# Mosfet.net
KiCad netlist of a schematic drawn in Altium Designer
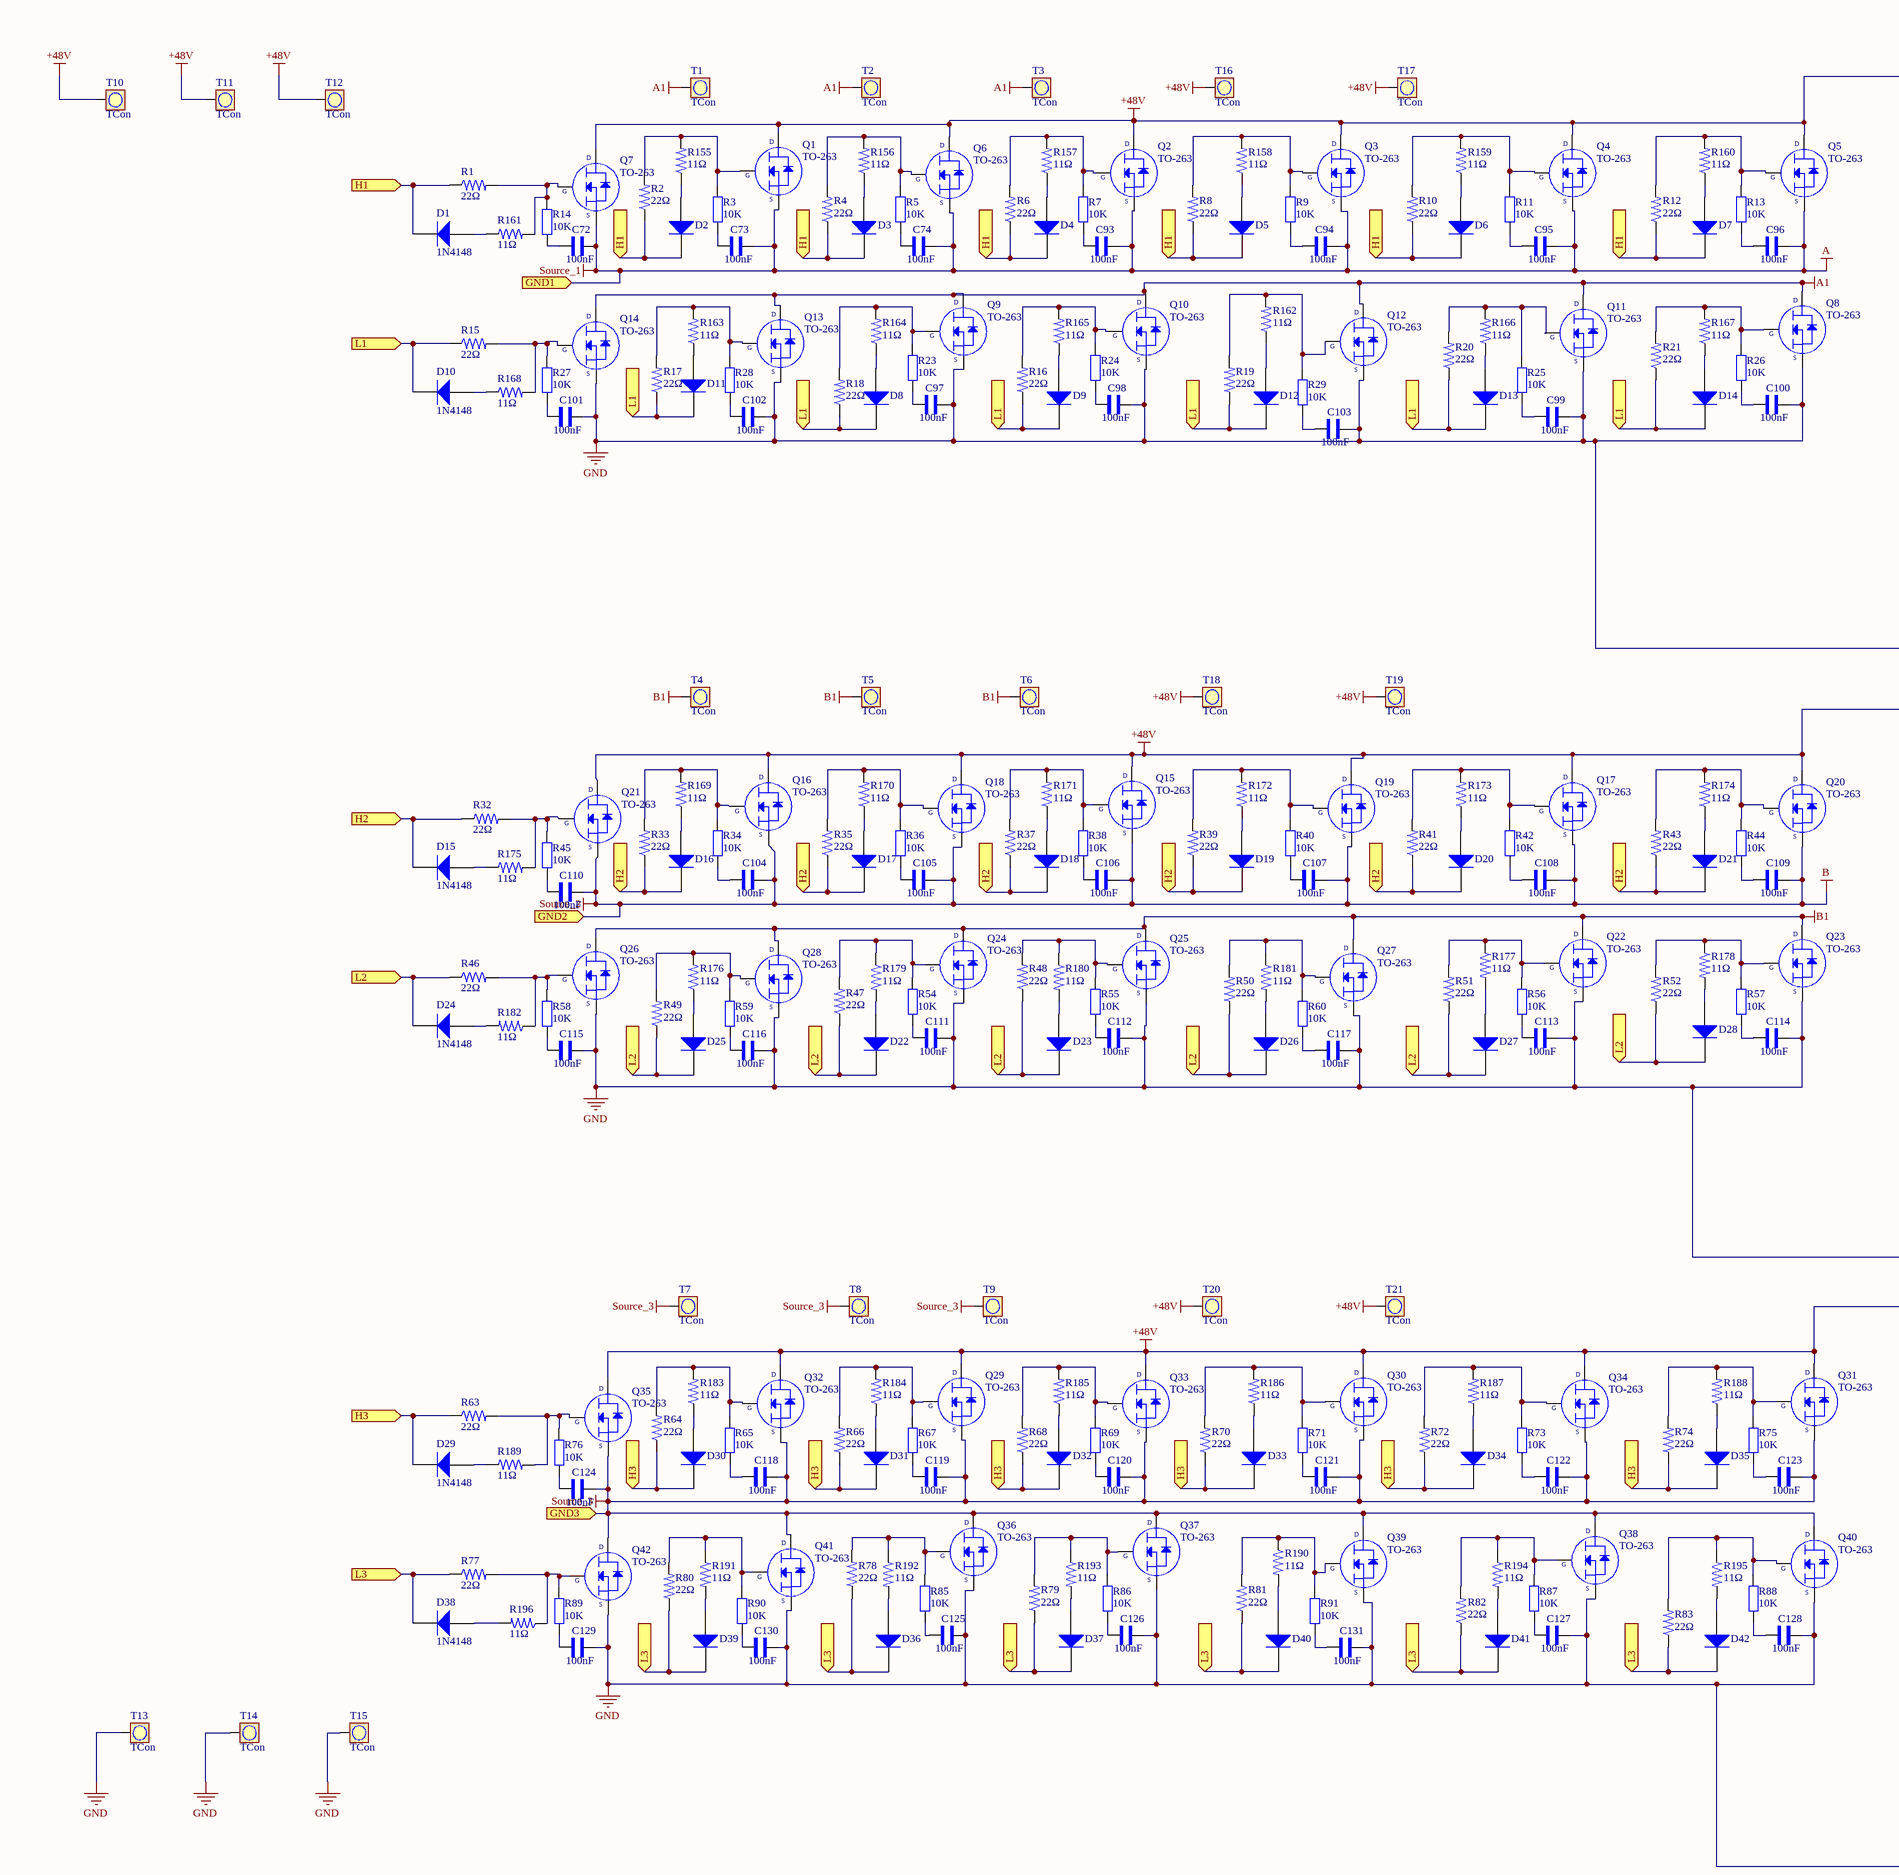
[diagram p0: Mosfet.SchDoc, left]
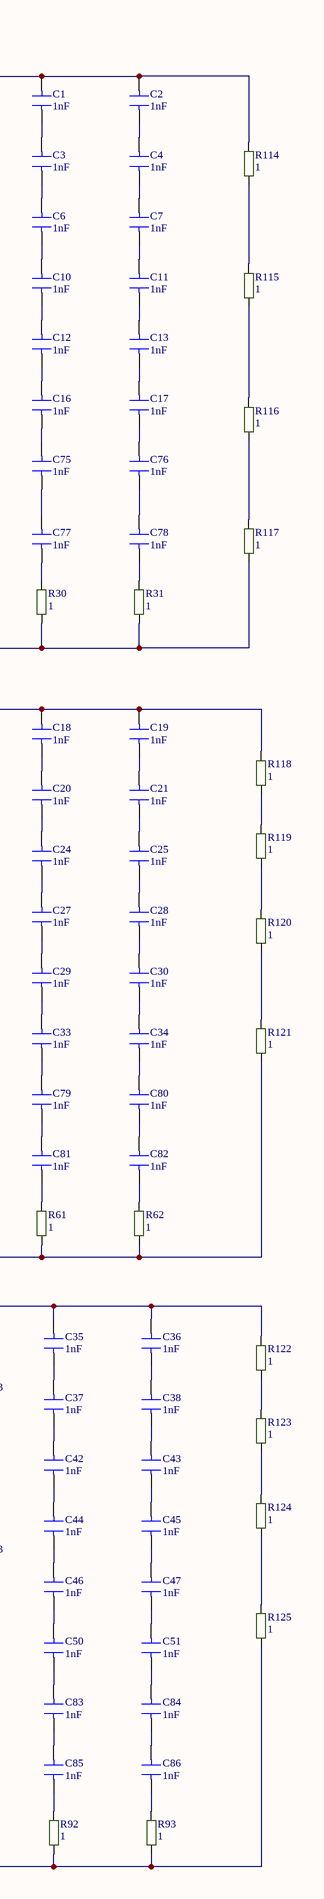
[diagram p1: Mosfet.SchDoc, right]

(export (version "E")
  (design (tool "Eeschema 10.0.6"))
  (components
    (comp (ref "C1")
      (value "1nF")
      (footprint "CAP 1206_3216 - 1.8MM")
      (libsource (lib "PROJE") (part "CAP 1nF 1206"))
    )
    (comp (ref "C2")
      (value "1nF")
      (footprint "CAP 1206_3216 - 1.8MM")
      (libsource (lib "PROJE") (part "CAP 1nF 1206"))
    )
    (comp (ref "C3")
      (value "1nF")
      (footprint "CAP 1206_3216 - 1.8MM")
      (libsource (lib "PROJE") (part "CAP 1nF 1206"))
    )
    (comp (ref "C4")
      (value "1nF")
      (footprint "CAP 1206_3216 - 1.8MM")
      (libsource (lib "PROJE") (part "CAP 1nF 1206"))
    )
    (comp (ref "C6")
      (value "1nF")
      (footprint "CAP 1206_3216 - 1.8MM")
      (libsource (lib "PROJE") (part "CAP 1nF 1206"))
    )
    (comp (ref "C7")
      (value "1nF")
      (footprint "CAP 1206_3216 - 1.8MM")
      (libsource (lib "PROJE") (part "CAP 1nF 1206"))
    )
    (comp (ref "C10")
      (value "1nF")
      (footprint "CAP 1206_3216 - 1.8MM")
      (libsource (lib "PROJE") (part "CAP 1nF 1206"))
    )
    (comp (ref "C11")
      (value "1nF")
      (footprint "CAP 1206_3216 - 1.8MM")
      (libsource (lib "PROJE") (part "CAP 1nF 1206"))
    )
    (comp (ref "C12")
      (value "1nF")
      (footprint "CAP 1206_3216 - 1.8MM")
      (libsource (lib "PROJE") (part "CAP 1nF 1206"))
    )
    (comp (ref "C13")
      (value "1nF")
      (footprint "CAP 1206_3216 - 1.8MM")
      (libsource (lib "PROJE") (part "CAP 1nF 1206"))
    )
    (comp (ref "C16")
      (value "1nF")
      (footprint "CAP 1206_3216 - 1.8MM")
      (libsource (lib "PROJE") (part "CAP 1nF 1206"))
    )
    (comp (ref "C17")
      (value "1nF")
      (footprint "CAP 1206_3216 - 1.8MM")
      (libsource (lib "PROJE") (part "CAP 1nF 1206"))
    )
    (comp (ref "C18")
      (value "1nF")
      (footprint "CAP 1206_3216 - 1.8MM")
      (libsource (lib "PROJE") (part "CAP 1nF 1206"))
    )
    (comp (ref "C19")
      (value "1nF")
      (footprint "CAP 1206_3216 - 1.8MM")
      (libsource (lib "PROJE") (part "CAP 1nF 1206"))
    )
    (comp (ref "C20")
      (value "1nF")
      (footprint "CAP 1206_3216 - 1.8MM")
      (libsource (lib "PROJE") (part "CAP 1nF 1206"))
    )
    (comp (ref "C21")
      (value "1nF")
      (footprint "CAP 1206_3216 - 1.8MM")
      (libsource (lib "PROJE") (part "CAP 1nF 1206"))
    )
    (comp (ref "C24")
      (value "1nF")
      (footprint "CAP 1206_3216 - 1.8MM")
      (libsource (lib "PROJE") (part "CAP 1nF 1206"))
    )
    (comp (ref "C25")
      (value "1nF")
      (footprint "CAP 1206_3216 - 1.8MM")
      (libsource (lib "PROJE") (part "CAP 1nF 1206"))
    )
    (comp (ref "C27")
      (value "1nF")
      (footprint "CAP 1206_3216 - 1.8MM")
      (libsource (lib "PROJE") (part "CAP 1nF 1206"))
    )
    (comp (ref "C28")
      (value "1nF")
      (footprint "CAP 1206_3216 - 1.8MM")
      (libsource (lib "PROJE") (part "CAP 1nF 1206"))
    )
    (comp (ref "C29")
      (value "1nF")
      (footprint "CAP 1206_3216 - 1.8MM")
      (libsource (lib "PROJE") (part "CAP 1nF 1206"))
    )
    (comp (ref "C30")
      (value "1nF")
      (footprint "CAP 1206_3216 - 1.8MM")
      (libsource (lib "PROJE") (part "CAP 1nF 1206"))
    )
    (comp (ref "C33")
      (value "1nF")
      (footprint "CAP 1206_3216 - 1.8MM")
      (libsource (lib "PROJE") (part "CAP 1nF 1206"))
    )
    (comp (ref "C34")
      (value "1nF")
      (footprint "CAP 1206_3216 - 1.8MM")
      (libsource (lib "PROJE") (part "CAP 1nF 1206"))
    )
    (comp (ref "C35")
      (value "1nF")
      (footprint "CAP 1206_3216 - 1.8MM")
      (libsource (lib "PROJE") (part "CAP 1nF 1206"))
    )
    (comp (ref "C36")
      (value "1nF")
      (footprint "CAP 1206_3216 - 1.8MM")
      (libsource (lib "PROJE") (part "CAP 1nF 1206"))
    )
    (comp (ref "C37")
      (value "1nF")
      (footprint "CAP 1206_3216 - 1.8MM")
      (libsource (lib "PROJE") (part "CAP 1nF 1206"))
    )
    (comp (ref "C38")
      (value "1nF")
      (footprint "CAP 1206_3216 - 1.8MM")
      (libsource (lib "PROJE") (part "CAP 1nF 1206"))
    )
    (comp (ref "C42")
      (value "1nF")
      (footprint "CAP 1206_3216 - 1.8MM")
      (libsource (lib "PROJE") (part "CAP 1nF 1206"))
    )
    (comp (ref "C43")
      (value "1nF")
      (footprint "CAP 1206_3216 - 1.8MM")
      (libsource (lib "PROJE") (part "CAP 1nF 1206"))
    )
    (comp (ref "C44")
      (value "1nF")
      (footprint "CAP 1206_3216 - 1.8MM")
      (libsource (lib "PROJE") (part "CAP 1nF 1206"))
    )
    (comp (ref "C45")
      (value "1nF")
      (footprint "CAP 1206_3216 - 1.8MM")
      (libsource (lib "PROJE") (part "CAP 1nF 1206"))
    )
    (comp (ref "C46")
      (value "1nF")
      (footprint "CAP 1206_3216 - 1.8MM")
      (libsource (lib "PROJE") (part "CAP 1nF 1206"))
    )
    (comp (ref "C47")
      (value "1nF")
      (footprint "CAP 1206_3216 - 1.8MM")
      (libsource (lib "PROJE") (part "CAP 1nF 1206"))
    )
    (comp (ref "C50")
      (value "1nF")
      (footprint "CAP 1206_3216 - 1.8MM")
      (libsource (lib "PROJE") (part "CAP 1nF 1206"))
    )
    (comp (ref "C51")
      (value "1nF")
      (footprint "CAP 1206_3216 - 1.8MM")
      (libsource (lib "PROJE") (part "CAP 1nF 1206"))
    )
    (comp (ref "C72")
      (value "100nF")
      (footprint "C-0805W")
      (fields
        (field (name "MF") "Wurth Electronics Inc")
        (field (name "MP") "885012207098")
        (field (name "BUYPART") "https://www.snapeda.com/parts/885012207098/Wurth%20Electronics%20Inc/view-part/4217223/?ref=eda")
      )
      (libsource (lib "PROJE") (part "CAP 100nF 50V SMT 0805"))
    )
    (comp (ref "C73")
      (value "100nF")
      (footprint "C-0805W")
      (fields
        (field (name "MF") "Wurth Electronics Inc")
        (field (name "MP") "885012207098")
        (field (name "BUYPART") "https://www.snapeda.com/parts/885012207098/Wurth%20Electronics%20Inc/view-part/4217223/?ref=eda")
      )
      (libsource (lib "PROJE") (part "CAP 100nF 50V SMT 0805"))
    )
    (comp (ref "C74")
      (value "100nF")
      (footprint "C-0805W")
      (fields
        (field (name "MF") "Wurth Electronics Inc")
        (field (name "MP") "885012207098")
        (field (name "BUYPART") "https://www.snapeda.com/parts/885012207098/Wurth%20Electronics%20Inc/view-part/4217223/?ref=eda")
      )
      (libsource (lib "PROJE") (part "CAP 100nF 50V SMT 0805"))
    )
    (comp (ref "C75")
      (value "1nF")
      (footprint "CAP 1206_3216 - 1.8MM")
      (libsource (lib "PROJE") (part "CAP 1nF 1206"))
    )
    (comp (ref "C76")
      (value "1nF")
      (footprint "CAP 1206_3216 - 1.8MM")
      (libsource (lib "PROJE") (part "CAP 1nF 1206"))
    )
    (comp (ref "C77")
      (value "1nF")
      (footprint "CAP 1206_3216 - 1.8MM")
      (libsource (lib "PROJE") (part "CAP 1nF 1206"))
    )
    (comp (ref "C78")
      (value "1nF")
      (footprint "CAP 1206_3216 - 1.8MM")
      (libsource (lib "PROJE") (part "CAP 1nF 1206"))
    )
    (comp (ref "C79")
      (value "1nF")
      (footprint "CAP 1206_3216 - 1.8MM")
      (libsource (lib "PROJE") (part "CAP 1nF 1206"))
    )
    (comp (ref "C80")
      (value "1nF")
      (footprint "CAP 1206_3216 - 1.8MM")
      (libsource (lib "PROJE") (part "CAP 1nF 1206"))
    )
    (comp (ref "C81")
      (value "1nF")
      (footprint "CAP 1206_3216 - 1.8MM")
      (libsource (lib "PROJE") (part "CAP 1nF 1206"))
    )
    (comp (ref "C82")
      (value "1nF")
      (footprint "CAP 1206_3216 - 1.8MM")
      (libsource (lib "PROJE") (part "CAP 1nF 1206"))
    )
    (comp (ref "C83")
      (value "1nF")
      (footprint "CAP 1206_3216 - 1.8MM")
      (libsource (lib "PROJE") (part "CAP 1nF 1206"))
    )
    (comp (ref "C84")
      (value "1nF")
      (footprint "CAP 1206_3216 - 1.8MM")
      (libsource (lib "PROJE") (part "CAP 1nF 1206"))
    )
    (comp (ref "C85")
      (value "1nF")
      (footprint "CAP 1206_3216 - 1.8MM")
      (libsource (lib "PROJE") (part "CAP 1nF 1206"))
    )
    (comp (ref "C86")
      (value "1nF")
      (footprint "CAP 1206_3216 - 1.8MM")
      (libsource (lib "PROJE") (part "CAP 1nF 1206"))
    )
    (comp (ref "C93")
      (value "100nF")
      (footprint "C-0805W")
      (fields
        (field (name "MF") "Wurth Electronics Inc")
        (field (name "MP") "885012207098")
        (field (name "BUYPART") "https://www.snapeda.com/parts/885012207098/Wurth%20Electronics%20Inc/view-part/4217223/?ref=eda")
      )
      (libsource (lib "PROJE") (part "CAP 100nF 50V SMT 0805"))
    )
    (comp (ref "C94")
      (value "100nF")
      (footprint "C-0805W")
      (fields
        (field (name "MF") "Wurth Electronics Inc")
        (field (name "MP") "885012207098")
        (field (name "BUYPART") "https://www.snapeda.com/parts/885012207098/Wurth%20Electronics%20Inc/view-part/4217223/?ref=eda")
      )
      (libsource (lib "PROJE") (part "CAP 100nF 50V SMT 0805"))
    )
    (comp (ref "C95")
      (value "100nF")
      (footprint "C-0805W")
      (fields
        (field (name "MF") "Wurth Electronics Inc")
        (field (name "MP") "885012207098")
        (field (name "BUYPART") "https://www.snapeda.com/parts/885012207098/Wurth%20Electronics%20Inc/view-part/4217223/?ref=eda")
      )
      (libsource (lib "PROJE") (part "CAP 100nF 50V SMT 0805"))
    )
    (comp (ref "C96")
      (value "100nF")
      (footprint "C-0805W")
      (fields
        (field (name "MF") "Wurth Electronics Inc")
        (field (name "MP") "885012207098")
        (field (name "BUYPART") "https://www.snapeda.com/parts/885012207098/Wurth%20Electronics%20Inc/view-part/4217223/?ref=eda")
      )
      (libsource (lib "PROJE") (part "CAP 100nF 50V SMT 0805"))
    )
    (comp (ref "C97")
      (value "100nF")
      (footprint "C-0805W")
      (fields
        (field (name "MF") "Wurth Electronics Inc")
        (field (name "MP") "885012207098")
        (field (name "BUYPART") "https://www.snapeda.com/parts/885012207098/Wurth%20Electronics%20Inc/view-part/4217223/?ref=eda")
      )
      (libsource (lib "PROJE") (part "CAP 100nF 50V SMT 0805"))
    )
    (comp (ref "C98")
      (value "100nF")
      (footprint "C-0805W")
      (fields
        (field (name "MF") "Wurth Electronics Inc")
        (field (name "MP") "885012207098")
        (field (name "BUYPART") "https://www.snapeda.com/parts/885012207098/Wurth%20Electronics%20Inc/view-part/4217223/?ref=eda")
      )
      (libsource (lib "PROJE") (part "CAP 100nF 50V SMT 0805"))
    )
    (comp (ref "C99")
      (value "100nF")
      (footprint "C-0805W")
      (fields
        (field (name "MF") "Wurth Electronics Inc")
        (field (name "MP") "885012207098")
        (field (name "BUYPART") "https://www.snapeda.com/parts/885012207098/Wurth%20Electronics%20Inc/view-part/4217223/?ref=eda")
      )
      (libsource (lib "PROJE") (part "CAP 100nF 50V SMT 0805"))
    )
    (comp (ref "C100")
      (value "100nF")
      (footprint "C-0805W")
      (fields
        (field (name "MF") "Wurth Electronics Inc")
        (field (name "MP") "885012207098")
        (field (name "BUYPART") "https://www.snapeda.com/parts/885012207098/Wurth%20Electronics%20Inc/view-part/4217223/?ref=eda")
      )
      (libsource (lib "PROJE") (part "CAP 100nF 50V SMT 0805"))
    )
    (comp (ref "C101")
      (value "100nF")
      (footprint "C-0805W")
      (fields
        (field (name "MF") "Wurth Electronics Inc")
        (field (name "MP") "885012207098")
        (field (name "BUYPART") "https://www.snapeda.com/parts/885012207098/Wurth%20Electronics%20Inc/view-part/4217223/?ref=eda")
      )
      (libsource (lib "PROJE") (part "CAP 100nF 50V SMT 0805"))
    )
    (comp (ref "C102")
      (value "100nF")
      (footprint "C-0805W")
      (fields
        (field (name "MF") "Wurth Electronics Inc")
        (field (name "MP") "885012207098")
        (field (name "BUYPART") "https://www.snapeda.com/parts/885012207098/Wurth%20Electronics%20Inc/view-part/4217223/?ref=eda")
      )
      (libsource (lib "PROJE") (part "CAP 100nF 50V SMT 0805"))
    )
    (comp (ref "C103")
      (value "100nF")
      (footprint "C-0805W")
      (fields
        (field (name "MF") "Wurth Electronics Inc")
        (field (name "MP") "885012207098")
        (field (name "BUYPART") "https://www.snapeda.com/parts/885012207098/Wurth%20Electronics%20Inc/view-part/4217223/?ref=eda")
      )
      (libsource (lib "PROJE") (part "CAP 100nF 50V SMT 0805"))
    )
    (comp (ref "C104")
      (value "100nF")
      (footprint "C-0805W")
      (fields
        (field (name "MF") "Wurth Electronics Inc")
        (field (name "MP") "885012207098")
        (field (name "BUYPART") "https://www.snapeda.com/parts/885012207098/Wurth%20Electronics%20Inc/view-part/4217223/?ref=eda")
      )
      (libsource (lib "PROJE") (part "CAP 100nF 50V SMT 0805"))
    )
    (comp (ref "C105")
      (value "100nF")
      (footprint "C-0805W")
      (fields
        (field (name "MF") "Wurth Electronics Inc")
        (field (name "MP") "885012207098")
        (field (name "BUYPART") "https://www.snapeda.com/parts/885012207098/Wurth%20Electronics%20Inc/view-part/4217223/?ref=eda")
      )
      (libsource (lib "PROJE") (part "CAP 100nF 50V SMT 0805"))
    )
    (comp (ref "C106")
      (value "100nF")
      (footprint "C-0805W")
      (fields
        (field (name "MF") "Wurth Electronics Inc")
        (field (name "MP") "885012207098")
        (field (name "BUYPART") "https://www.snapeda.com/parts/885012207098/Wurth%20Electronics%20Inc/view-part/4217223/?ref=eda")
      )
      (libsource (lib "PROJE") (part "CAP 100nF 50V SMT 0805"))
    )
    (comp (ref "C107")
      (value "100nF")
      (footprint "C-0805W")
      (fields
        (field (name "MF") "Wurth Electronics Inc")
        (field (name "MP") "885012207098")
        (field (name "BUYPART") "https://www.snapeda.com/parts/885012207098/Wurth%20Electronics%20Inc/view-part/4217223/?ref=eda")
      )
      (libsource (lib "PROJE") (part "CAP 100nF 50V SMT 0805"))
    )
    (comp (ref "C108")
      (value "100nF")
      (footprint "C-0805W")
      (fields
        (field (name "MF") "Wurth Electronics Inc")
        (field (name "MP") "885012207098")
        (field (name "BUYPART") "https://www.snapeda.com/parts/885012207098/Wurth%20Electronics%20Inc/view-part/4217223/?ref=eda")
      )
      (libsource (lib "PROJE") (part "CAP 100nF 50V SMT 0805"))
    )
    (comp (ref "C109")
      (value "100nF")
      (footprint "C-0805W")
      (fields
        (field (name "MF") "Wurth Electronics Inc")
        (field (name "MP") "885012207098")
        (field (name "BUYPART") "https://www.snapeda.com/parts/885012207098/Wurth%20Electronics%20Inc/view-part/4217223/?ref=eda")
      )
      (libsource (lib "PROJE") (part "CAP 100nF 50V SMT 0805"))
    )
    (comp (ref "C110")
      (value "100nF")
      (footprint "C-0805W")
      (fields
        (field (name "MF") "Wurth Electronics Inc")
        (field (name "MP") "885012207098")
        (field (name "BUYPART") "https://www.snapeda.com/parts/885012207098/Wurth%20Electronics%20Inc/view-part/4217223/?ref=eda")
      )
      (libsource (lib "PROJE") (part "CAP 100nF 50V SMT 0805"))
    )
    (comp (ref "C111")
      (value "100nF")
      (footprint "C-0805W")
      (fields
        (field (name "MF") "Wurth Electronics Inc")
        (field (name "MP") "885012207098")
        (field (name "BUYPART") "https://www.snapeda.com/parts/885012207098/Wurth%20Electronics%20Inc/view-part/4217223/?ref=eda")
      )
      (libsource (lib "PROJE") (part "CAP 100nF 50V SMT 0805"))
    )
    (comp (ref "C112")
      (value "100nF")
      (footprint "C-0805W")
      (fields
        (field (name "MF") "Wurth Electronics Inc")
        (field (name "MP") "885012207098")
        (field (name "BUYPART") "https://www.snapeda.com/parts/885012207098/Wurth%20Electronics%20Inc/view-part/4217223/?ref=eda")
      )
      (libsource (lib "PROJE") (part "CAP 100nF 50V SMT 0805"))
    )
    (comp (ref "C113")
      (value "100nF")
      (footprint "C-0805W")
      (fields
        (field (name "MF") "Wurth Electronics Inc")
        (field (name "MP") "885012207098")
        (field (name "BUYPART") "https://www.snapeda.com/parts/885012207098/Wurth%20Electronics%20Inc/view-part/4217223/?ref=eda")
      )
      (libsource (lib "PROJE") (part "CAP 100nF 50V SMT 0805"))
    )
    (comp (ref "C114")
      (value "100nF")
      (footprint "C-0805W")
      (fields
        (field (name "MF") "Wurth Electronics Inc")
        (field (name "MP") "885012207098")
        (field (name "BUYPART") "https://www.snapeda.com/parts/885012207098/Wurth%20Electronics%20Inc/view-part/4217223/?ref=eda")
      )
      (libsource (lib "PROJE") (part "CAP 100nF 50V SMT 0805"))
    )
    (comp (ref "C115")
      (value "100nF")
      (footprint "C-0805W")
      (fields
        (field (name "MF") "Wurth Electronics Inc")
        (field (name "MP") "885012207098")
        (field (name "BUYPART") "https://www.snapeda.com/parts/885012207098/Wurth%20Electronics%20Inc/view-part/4217223/?ref=eda")
      )
      (libsource (lib "PROJE") (part "CAP 100nF 50V SMT 0805"))
    )
    (comp (ref "C116")
      (value "100nF")
      (footprint "C-0805W")
      (fields
        (field (name "MF") "Wurth Electronics Inc")
        (field (name "MP") "885012207098")
        (field (name "BUYPART") "https://www.snapeda.com/parts/885012207098/Wurth%20Electronics%20Inc/view-part/4217223/?ref=eda")
      )
      (libsource (lib "PROJE") (part "CAP 100nF 50V SMT 0805"))
    )
    (comp (ref "C117")
      (value "100nF")
      (footprint "C-0805W")
      (fields
        (field (name "MF") "Wurth Electronics Inc")
        (field (name "MP") "885012207098")
        (field (name "BUYPART") "https://www.snapeda.com/parts/885012207098/Wurth%20Electronics%20Inc/view-part/4217223/?ref=eda")
      )
      (libsource (lib "PROJE") (part "CAP 100nF 50V SMT 0805"))
    )
    (comp (ref "C118")
      (value "100nF")
      (footprint "C-0805W")
      (fields
        (field (name "MF") "Wurth Electronics Inc")
        (field (name "MP") "885012207098")
        (field (name "BUYPART") "https://www.snapeda.com/parts/885012207098/Wurth%20Electronics%20Inc/view-part/4217223/?ref=eda")
      )
      (libsource (lib "PROJE") (part "CAP 100nF 50V SMT 0805"))
    )
    (comp (ref "C119")
      (value "100nF")
      (footprint "C-0805W")
      (fields
        (field (name "MF") "Wurth Electronics Inc")
        (field (name "MP") "885012207098")
        (field (name "BUYPART") "https://www.snapeda.com/parts/885012207098/Wurth%20Electronics%20Inc/view-part/4217223/?ref=eda")
      )
      (libsource (lib "PROJE") (part "CAP 100nF 50V SMT 0805"))
    )
    (comp (ref "C120")
      (value "100nF")
      (footprint "C-0805W")
      (fields
        (field (name "MF") "Wurth Electronics Inc")
        (field (name "MP") "885012207098")
        (field (name "BUYPART") "https://www.snapeda.com/parts/885012207098/Wurth%20Electronics%20Inc/view-part/4217223/?ref=eda")
      )
      (libsource (lib "PROJE") (part "CAP 100nF 50V SMT 0805"))
    )
    (comp (ref "C121")
      (value "100nF")
      (footprint "C-0805W")
      (fields
        (field (name "MF") "Wurth Electronics Inc")
        (field (name "MP") "885012207098")
        (field (name "BUYPART") "https://www.snapeda.com/parts/885012207098/Wurth%20Electronics%20Inc/view-part/4217223/?ref=eda")
      )
      (libsource (lib "PROJE") (part "CAP 100nF 50V SMT 0805"))
    )
    (comp (ref "C122")
      (value "100nF")
      (footprint "C-0805W")
      (fields
        (field (name "MF") "Wurth Electronics Inc")
        (field (name "MP") "885012207098")
        (field (name "BUYPART") "https://www.snapeda.com/parts/885012207098/Wurth%20Electronics%20Inc/view-part/4217223/?ref=eda")
      )
      (libsource (lib "PROJE") (part "CAP 100nF 50V SMT 0805"))
    )
    (comp (ref "C123")
      (value "100nF")
      (footprint "C-0805W")
      (fields
        (field (name "MF") "Wurth Electronics Inc")
        (field (name "MP") "885012207098")
        (field (name "BUYPART") "https://www.snapeda.com/parts/885012207098/Wurth%20Electronics%20Inc/view-part/4217223/?ref=eda")
      )
      (libsource (lib "PROJE") (part "CAP 100nF 50V SMT 0805"))
    )
    (comp (ref "C124")
      (value "100nF")
      (footprint "C-0805W")
      (fields
        (field (name "MF") "Wurth Electronics Inc")
        (field (name "MP") "885012207098")
        (field (name "BUYPART") "https://www.snapeda.com/parts/885012207098/Wurth%20Electronics%20Inc/view-part/4217223/?ref=eda")
      )
      (libsource (lib "PROJE") (part "CAP 100nF 50V SMT 0805"))
    )
    (comp (ref "C125")
      (value "100nF")
      (footprint "C-0805W")
      (fields
        (field (name "MF") "Wurth Electronics Inc")
        (field (name "MP") "885012207098")
        (field (name "BUYPART") "https://www.snapeda.com/parts/885012207098/Wurth%20Electronics%20Inc/view-part/4217223/?ref=eda")
      )
      (libsource (lib "PROJE") (part "CAP 100nF 50V SMT 0805"))
    )
    (comp (ref "C126")
      (value "100nF")
      (footprint "C-0805W")
      (fields
        (field (name "MF") "Wurth Electronics Inc")
        (field (name "MP") "885012207098")
        (field (name "BUYPART") "https://www.snapeda.com/parts/885012207098/Wurth%20Electronics%20Inc/view-part/4217223/?ref=eda")
      )
      (libsource (lib "PROJE") (part "CAP 100nF 50V SMT 0805"))
    )
    (comp (ref "C127")
      (value "100nF")
      (footprint "C-0805W")
      (fields
        (field (name "MF") "Wurth Electronics Inc")
        (field (name "MP") "885012207098")
        (field (name "BUYPART") "https://www.snapeda.com/parts/885012207098/Wurth%20Electronics%20Inc/view-part/4217223/?ref=eda")
      )
      (libsource (lib "PROJE") (part "CAP 100nF 50V SMT 0805"))
    )
    (comp (ref "C128")
      (value "100nF")
      (footprint "C-0805W")
      (fields
        (field (name "MF") "Wurth Electronics Inc")
        (field (name "MP") "885012207098")
        (field (name "BUYPART") "https://www.snapeda.com/parts/885012207098/Wurth%20Electronics%20Inc/view-part/4217223/?ref=eda")
      )
      (libsource (lib "PROJE") (part "CAP 100nF 50V SMT 0805"))
    )
    (comp (ref "C129")
      (value "100nF")
      (footprint "C-0805W")
      (fields
        (field (name "MF") "Wurth Electronics Inc")
        (field (name "MP") "885012207098")
        (field (name "BUYPART") "https://www.snapeda.com/parts/885012207098/Wurth%20Electronics%20Inc/view-part/4217223/?ref=eda")
      )
      (libsource (lib "PROJE") (part "CAP 100nF 50V SMT 0805"))
    )
    (comp (ref "C130")
      (value "100nF")
      (footprint "C-0805W")
      (fields
        (field (name "MF") "Wurth Electronics Inc")
        (field (name "MP") "885012207098")
        (field (name "BUYPART") "https://www.snapeda.com/parts/885012207098/Wurth%20Electronics%20Inc/view-part/4217223/?ref=eda")
      )
      (libsource (lib "PROJE") (part "CAP 100nF 50V SMT 0805"))
    )
    (comp (ref "C131")
      (value "100nF")
      (footprint "C-0805W")
      (fields
        (field (name "MF") "Wurth Electronics Inc")
        (field (name "MP") "885012207098")
        (field (name "BUYPART") "https://www.snapeda.com/parts/885012207098/Wurth%20Electronics%20Inc/view-part/4217223/?ref=eda")
      )
      (libsource (lib "PROJE") (part "CAP 100nF 50V SMT 0805"))
    )
    (comp (ref "D1")
      (value "1N4148 Diyot")
      (footprint "SOD-123")
      (description "DIODE GEN PURP 100V 150MA SOD123")
      (fields (field (name "DEGER") "1N4148"))
      (libsource (lib "PROJE") (part "1N4148"))
    )
    (comp (ref "D2")
      (value "1N4148 Diyot")
      (footprint "SOD-123")
      (description "DIODE GEN PURP 100V 150MA SOD123")
      (libsource (lib "PROJE") (part "1N4148"))
    )
    (comp (ref "D3")
      (value "1N4148 Diyot")
      (footprint "SOD-123")
      (description "DIODE GEN PURP 100V 150MA SOD123")
      (libsource (lib "PROJE") (part "1N4148"))
    )
    (comp (ref "D4")
      (value "1N4148 Diyot")
      (footprint "SOD-123")
      (description "DIODE GEN PURP 100V 150MA SOD123")
      (libsource (lib "PROJE") (part "1N4148"))
    )
    (comp (ref "D5")
      (value "1N4148 Diyot")
      (footprint "SOD-123")
      (description "DIODE GEN PURP 100V 150MA SOD123")
      (libsource (lib "PROJE") (part "1N4148"))
    )
    (comp (ref "D6")
      (value "1N4148 Diyot")
      (footprint "SOD-123")
      (description "DIODE GEN PURP 100V 150MA SOD123")
      (libsource (lib "PROJE") (part "1N4148"))
    )
    (comp (ref "D7")
      (value "1N4148 Diyot")
      (footprint "SOD-123")
      (description "DIODE GEN PURP 100V 150MA SOD123")
      (libsource (lib "PROJE") (part "1N4148"))
    )
    (comp (ref "D8")
      (value "1N4148 Diyot")
      (footprint "SOD-123")
      (description "DIODE GEN PURP 100V 150MA SOD123")
      (libsource (lib "PROJE") (part "1N4148"))
    )
    (comp (ref "D9")
      (value "1N4148 Diyot")
      (footprint "SOD-123")
      (description "DIODE GEN PURP 100V 150MA SOD123")
      (libsource (lib "PROJE") (part "1N4148"))
    )
    (comp (ref "D10")
      (value "1N4148 Diyot")
      (footprint "SOD-123")
      (description "DIODE GEN PURP 100V 150MA SOD123")
      (fields (field (name "DEGER") "1N4148"))
      (libsource (lib "PROJE") (part "1N4148"))
    )
    (comp (ref "D11")
      (value "1N4148 Diyot")
      (footprint "SOD-123")
      (description "DIODE GEN PURP 100V 150MA SOD123")
      (libsource (lib "PROJE") (part "1N4148"))
    )
    (comp (ref "D12")
      (value "1N4148 Diyot")
      (footprint "SOD-123")
      (description "DIODE GEN PURP 100V 150MA SOD123")
      (libsource (lib "PROJE") (part "1N4148"))
    )
    (comp (ref "D13")
      (value "1N4148 Diyot")
      (footprint "SOD-123")
      (description "DIODE GEN PURP 100V 150MA SOD123")
      (libsource (lib "PROJE") (part "1N4148"))
    )
    (comp (ref "D14")
      (value "1N4148 Diyot")
      (footprint "SOD-123")
      (description "DIODE GEN PURP 100V 150MA SOD123")
      (libsource (lib "PROJE") (part "1N4148"))
    )
    (comp (ref "D15")
      (value "1N4148 Diyot")
      (footprint "SOD-123")
      (description "DIODE GEN PURP 100V 150MA SOD123")
      (fields (field (name "DEGER") "1N4148"))
      (libsource (lib "PROJE") (part "1N4148"))
    )
    (comp (ref "D16")
      (value "1N4148 Diyot")
      (footprint "SOD-123")
      (description "DIODE GEN PURP 100V 150MA SOD123")
      (libsource (lib "PROJE") (part "1N4148"))
    )
    (comp (ref "D17")
      (value "1N4148 Diyot")
      (footprint "SOD-123")
      (description "DIODE GEN PURP 100V 150MA SOD123")
      (libsource (lib "PROJE") (part "1N4148"))
    )
    (comp (ref "D18")
      (value "1N4148 Diyot")
      (footprint "SOD-123")
      (description "DIODE GEN PURP 100V 150MA SOD123")
      (libsource (lib "PROJE") (part "1N4148"))
    )
    (comp (ref "D19")
      (value "1N4148 Diyot")
      (footprint "SOD-123")
      (description "DIODE GEN PURP 100V 150MA SOD123")
      (libsource (lib "PROJE") (part "1N4148"))
    )
    (comp (ref "D20")
      (value "1N4148 Diyot")
      (footprint "SOD-123")
      (description "DIODE GEN PURP 100V 150MA SOD123")
      (libsource (lib "PROJE") (part "1N4148"))
    )
    (comp (ref "D21")
      (value "1N4148 Diyot")
      (footprint "SOD-123")
      (description "DIODE GEN PURP 100V 150MA SOD123")
      (libsource (lib "PROJE") (part "1N4148"))
    )
    (comp (ref "D22")
      (value "1N4148 Diyot")
      (footprint "SOD-123")
      (description "DIODE GEN PURP 100V 150MA SOD123")
      (libsource (lib "PROJE") (part "1N4148"))
    )
    (comp (ref "D23")
      (value "1N4148 Diyot")
      (footprint "SOD-123")
      (description "DIODE GEN PURP 100V 150MA SOD123")
      (libsource (lib "PROJE") (part "1N4148"))
    )
    (comp (ref "D24")
      (value "1N4148 Diyot")
      (footprint "SOD-123")
      (description "DIODE GEN PURP 100V 150MA SOD123")
      (fields (field (name "DEGER") "1N4148"))
      (libsource (lib "PROJE") (part "1N4148"))
    )
    (comp (ref "D25")
      (value "1N4148 Diyot")
      (footprint "SOD-123")
      (description "DIODE GEN PURP 100V 150MA SOD123")
      (libsource (lib "PROJE") (part "1N4148"))
    )
    (comp (ref "D26")
      (value "1N4148 Diyot")
      (footprint "SOD-123")
      (description "DIODE GEN PURP 100V 150MA SOD123")
      (libsource (lib "PROJE") (part "1N4148"))
    )
    (comp (ref "D27")
      (value "1N4148 Diyot")
      (footprint "SOD-123")
      (description "DIODE GEN PURP 100V 150MA SOD123")
      (libsource (lib "PROJE") (part "1N4148"))
    )
    (comp (ref "D28")
      (value "1N4148 Diyot")
      (footprint "SOD-123")
      (description "DIODE GEN PURP 100V 150MA SOD123")
      (libsource (lib "PROJE") (part "1N4148"))
    )
    (comp (ref "D29")
      (value "1N4148 Diyot")
      (footprint "SOD-123")
      (description "DIODE GEN PURP 100V 150MA SOD123")
      (fields (field (name "DEGER") "1N4148"))
      (libsource (lib "PROJE") (part "1N4148"))
    )
    (comp (ref "D30")
      (value "1N4148 Diyot")
      (footprint "SOD-123")
      (description "DIODE GEN PURP 100V 150MA SOD123")
      (libsource (lib "PROJE") (part "1N4148"))
    )
    (comp (ref "D31")
      (value "1N4148 Diyot")
      (footprint "SOD-123")
      (description "DIODE GEN PURP 100V 150MA SOD123")
      (libsource (lib "PROJE") (part "1N4148"))
    )
    (comp (ref "D32")
      (value "1N4148 Diyot")
      (footprint "SOD-123")
      (description "DIODE GEN PURP 100V 150MA SOD123")
      (libsource (lib "PROJE") (part "1N4148"))
    )
    (comp (ref "D33")
      (value "1N4148 Diyot")
      (footprint "SOD-123")
      (description "DIODE GEN PURP 100V 150MA SOD123")
      (libsource (lib "PROJE") (part "1N4148"))
    )
    (comp (ref "D34")
      (value "1N4148 Diyot")
      (footprint "SOD-123")
      (description "DIODE GEN PURP 100V 150MA SOD123")
      (libsource (lib "PROJE") (part "1N4148"))
    )
    (comp (ref "D35")
      (value "1N4148 Diyot")
      (footprint "SOD-123")
      (description "DIODE GEN PURP 100V 150MA SOD123")
      (libsource (lib "PROJE") (part "1N4148"))
    )
    (comp (ref "D36")
      (value "1N4148 Diyot")
      (footprint "SOD-123")
      (description "DIODE GEN PURP 100V 150MA SOD123")
      (libsource (lib "PROJE") (part "1N4148"))
    )
    (comp (ref "D37")
      (value "1N4148 Diyot")
      (footprint "SOD-123")
      (description "DIODE GEN PURP 100V 150MA SOD123")
      (libsource (lib "PROJE") (part "1N4148"))
    )
    (comp (ref "D38")
      (value "1N4148 Diyot")
      (footprint "SOD-123")
      (description "DIODE GEN PURP 100V 150MA SOD123")
      (fields (field (name "DEGER") "1N4148"))
      (libsource (lib "PROJE") (part "1N4148"))
    )
    (comp (ref "D39")
      (value "1N4148 Diyot")
      (footprint "SOD-123")
      (description "DIODE GEN PURP 100V 150MA SOD123")
      (libsource (lib "PROJE") (part "1N4148"))
    )
    (comp (ref "D40")
      (value "1N4148 Diyot")
      (footprint "SOD-123")
      (description "DIODE GEN PURP 100V 150MA SOD123")
      (libsource (lib "PROJE") (part "1N4148"))
    )
    (comp (ref "D41")
      (value "1N4148 Diyot")
      (footprint "SOD-123")
      (description "DIODE GEN PURP 100V 150MA SOD123")
      (libsource (lib "PROJE") (part "1N4148"))
    )
    (comp (ref "D42")
      (value "1N4148 Diyot")
      (footprint "SOD-123")
      (description "DIODE GEN PURP 100V 150MA SOD123")
      (libsource (lib "PROJE") (part "1N4148"))
    )
    (comp (ref "Q1") (value "TO-263") (footprint "DPAK_TO263") (libsource (lib "PROJE") (part "TO-263")))
    (comp (ref "Q2") (value "TO-263") (footprint "DPAK_TO263") (libsource (lib "PROJE") (part "TO-263")))
    (comp (ref "Q3") (value "TO-263") (footprint "DPAK_TO263") (libsource (lib "PROJE") (part "TO-263")))
    (comp (ref "Q4") (value "TO-263") (footprint "DPAK_TO263") (libsource (lib "PROJE") (part "TO-263")))
    (comp (ref "Q5") (value "TO-263") (footprint "DPAK_TO263") (libsource (lib "PROJE") (part "TO-263")))
    (comp (ref "Q6") (value "TO-263") (footprint "DPAK_TO263") (libsource (lib "PROJE") (part "TO-263")))
    (comp (ref "Q7") (value "TO-263") (footprint "DPAK_TO263") (libsource (lib "PROJE") (part "TO-263")))
    (comp (ref "Q8") (value "TO-263") (footprint "DPAK_TO263") (libsource (lib "PROJE") (part "TO-263")))
    (comp (ref "Q9") (value "TO-263") (footprint "DPAK_TO263") (libsource (lib "PROJE") (part "TO-263")))
    (comp (ref "Q10") (value "TO-263") (footprint "DPAK_TO263") (libsource (lib "PROJE") (part "TO-263")))
    (comp (ref "Q11") (value "TO-263") (footprint "DPAK_TO263") (libsource (lib "PROJE") (part "TO-263")))
    (comp (ref "Q12") (value "TO-263") (footprint "DPAK_TO263") (libsource (lib "PROJE") (part "TO-263")))
    (comp (ref "Q13") (value "TO-263") (footprint "DPAK_TO263") (libsource (lib "PROJE") (part "TO-263")))
    (comp (ref "Q14") (value "TO-263") (footprint "DPAK_TO263") (libsource (lib "PROJE") (part "TO-263")))
    (comp (ref "Q15") (value "TO-263") (footprint "DPAK_TO263") (libsource (lib "PROJE") (part "TO-263")))
    (comp (ref "Q16") (value "TO-263") (footprint "DPAK_TO263") (libsource (lib "PROJE") (part "TO-263")))
    (comp (ref "Q17") (value "TO-263") (footprint "DPAK_TO263") (libsource (lib "PROJE") (part "TO-263")))
    (comp (ref "Q18") (value "TO-263") (footprint "DPAK_TO263") (libsource (lib "PROJE") (part "TO-263")))
    (comp (ref "Q19") (value "TO-263") (footprint "DPAK_TO263") (libsource (lib "PROJE") (part "TO-263")))
    (comp (ref "Q20") (value "TO-263") (footprint "DPAK_TO263") (libsource (lib "PROJE") (part "TO-263")))
    (comp (ref "Q21") (value "TO-263") (footprint "DPAK_TO263") (libsource (lib "PROJE") (part "TO-263")))
    (comp (ref "Q22") (value "TO-263") (footprint "DPAK_TO263") (libsource (lib "PROJE") (part "TO-263")))
    (comp (ref "Q23") (value "TO-263") (footprint "DPAK_TO263") (libsource (lib "PROJE") (part "TO-263")))
    (comp (ref "Q24") (value "TO-263") (footprint "DPAK_TO263") (libsource (lib "PROJE") (part "TO-263")))
    (comp (ref "Q25") (value "TO-263") (footprint "DPAK_TO263") (libsource (lib "PROJE") (part "TO-263")))
    (comp (ref "Q26") (value "TO-263") (footprint "DPAK_TO263") (libsource (lib "PROJE") (part "TO-263")))
    (comp (ref "Q27") (value "TO-263") (footprint "DPAK_TO263") (libsource (lib "PROJE") (part "TO-263")))
    (comp (ref "Q28") (value "TO-263") (footprint "DPAK_TO263") (libsource (lib "PROJE") (part "TO-263")))
    (comp (ref "Q29") (value "TO-263") (footprint "DPAK_TO263") (libsource (lib "PROJE") (part "TO-263")))
    (comp (ref "Q30") (value "TO-263") (footprint "DPAK_TO263") (libsource (lib "PROJE") (part "TO-263")))
    (comp (ref "Q31") (value "TO-263") (footprint "DPAK_TO263") (libsource (lib "PROJE") (part "TO-263")))
    (comp (ref "Q32") (value "TO-263") (footprint "DPAK_TO263") (libsource (lib "PROJE") (part "TO-263")))
    (comp (ref "Q33") (value "TO-263") (footprint "DPAK_TO263") (libsource (lib "PROJE") (part "TO-263")))
    (comp (ref "Q34") (value "TO-263") (footprint "DPAK_TO263") (libsource (lib "PROJE") (part "TO-263")))
    (comp (ref "Q35") (value "TO-263") (footprint "DPAK_TO263") (libsource (lib "PROJE") (part "TO-263")))
    (comp (ref "Q36") (value "TO-263") (footprint "DPAK_TO263") (libsource (lib "PROJE") (part "TO-263")))
    (comp (ref "Q37") (value "TO-263") (footprint "DPAK_TO263") (libsource (lib "PROJE") (part "TO-263")))
    (comp (ref "Q38") (value "TO-263") (footprint "DPAK_TO263") (libsource (lib "PROJE") (part "TO-263")))
    (comp (ref "Q39") (value "TO-263") (footprint "DPAK_TO263") (libsource (lib "PROJE") (part "TO-263")))
    (comp (ref "Q40") (value "TO-263") (footprint "DPAK_TO263") (libsource (lib "PROJE") (part "TO-263")))
    (comp (ref "Q41") (value "TO-263") (footprint "DPAK_TO263") (libsource (lib "PROJE") (part "TO-263")))
    (comp (ref "Q42") (value "TO-263") (footprint "DPAK_TO263") (libsource (lib "PROJE") (part "TO-263")))
    (comp (ref "R1")
      (value "22Ω")
      (footprint "R-1206W")
      (description "CRG1206 1% 22R")
      (fields (field (name "MP") "1623463-1"))
      (libsource (lib "PROJE") (part "RES 22Ω 1206"))
    )
    (comp (ref "R2")
      (value "22Ω")
      (footprint "R-1206W")
      (description "CRG1206 1% 22R")
      (fields (field (name "MP") "1623463-1"))
      (libsource (lib "PROJE") (part "RES 22Ω 1206"))
    )
    (comp (ref "R3")
      (value "RES SMD 10K OHM 1% 1/8W 0805")
      (footprint "R-0805W")
      (description "10 kOhms ±1% 0.125W, 1/8W Chip Resistor 0805 (2012 Metric) Moisture Resistant Thick Film")
      (fields (field (name "DEGER") "10K"))
      (libsource (lib "PROJE") (part "10K 0805"))
    )
    (comp (ref "R4")
      (value "22Ω")
      (footprint "R-1206W")
      (description "CRG1206 1% 22R")
      (fields (field (name "MP") "1623463-1"))
      (libsource (lib "PROJE") (part "RES 22Ω 1206"))
    )
    (comp (ref "R5")
      (value "RES SMD 10K OHM 1% 1/8W 0805")
      (footprint "R-0805W")
      (description "10 kOhms ±1% 0.125W, 1/8W Chip Resistor 0805 (2012 Metric) Moisture Resistant Thick Film")
      (fields (field (name "DEGER") "10K"))
      (libsource (lib "PROJE") (part "10K 0805"))
    )
    (comp (ref "R6")
      (value "22Ω")
      (footprint "R-1206W")
      (description "CRG1206 1% 22R")
      (fields (field (name "MP") "1623463-1"))
      (libsource (lib "PROJE") (part "RES 22Ω 1206"))
    )
    (comp (ref "R7")
      (value "RES SMD 10K OHM 1% 1/8W 0805")
      (footprint "R-0805W")
      (description "10 kOhms ±1% 0.125W, 1/8W Chip Resistor 0805 (2012 Metric) Moisture Resistant Thick Film")
      (fields (field (name "DEGER") "10K"))
      (libsource (lib "PROJE") (part "10K 0805"))
    )
    (comp (ref "R8")
      (value "22Ω")
      (footprint "R-1206W")
      (description "CRG1206 1% 22R")
      (fields (field (name "MP") "1623463-1"))
      (libsource (lib "PROJE") (part "RES 22Ω 1206"))
    )
    (comp (ref "R9")
      (value "RES SMD 10K OHM 1% 1/8W 0805")
      (footprint "R-0805W")
      (description "10 kOhms ±1% 0.125W, 1/8W Chip Resistor 0805 (2012 Metric) Moisture Resistant Thick Film")
      (fields (field (name "DEGER") "10K"))
      (libsource (lib "PROJE") (part "10K 0805"))
    )
    (comp (ref "R10")
      (value "22Ω")
      (footprint "R-1206W")
      (description "CRG1206 1% 22R")
      (fields (field (name "MP") "1623463-1"))
      (libsource (lib "PROJE") (part "RES 22Ω 1206"))
    )
    (comp (ref "R11")
      (value "RES SMD 10K OHM 1% 1/8W 0805")
      (footprint "R-0805W")
      (description "10 kOhms ±1% 0.125W, 1/8W Chip Resistor 0805 (2012 Metric) Moisture Resistant Thick Film")
      (fields (field (name "DEGER") "10K"))
      (libsource (lib "PROJE") (part "10K 0805"))
    )
    (comp (ref "R12")
      (value "22Ω")
      (footprint "R-1206W")
      (description "CRG1206 1% 22R")
      (fields (field (name "MP") "1623463-1"))
      (libsource (lib "PROJE") (part "RES 22Ω 1206"))
    )
    (comp (ref "R13")
      (value "RES SMD 10K OHM 1% 1/8W 0805")
      (footprint "R-0805W")
      (description "10 kOhms ±1% 0.125W, 1/8W Chip Resistor 0805 (2012 Metric) Moisture Resistant Thick Film")
      (fields (field (name "DEGER") "10K"))
      (libsource (lib "PROJE") (part "10K 0805"))
    )
    (comp (ref "R14")
      (value "RES SMD 10K OHM 1% 1/8W 0805")
      (footprint "R-0805W")
      (description "10 kOhms ±1% 0.125W, 1/8W Chip Resistor 0805 (2012 Metric) Moisture Resistant Thick Film")
      (fields (field (name "DEGER") "10K"))
      (libsource (lib "PROJE") (part "10K 0805"))
    )
    (comp (ref "R15")
      (value "22Ω")
      (footprint "R-1206W")
      (description "CRG1206 1% 22R")
      (fields (field (name "MP") "1623463-1"))
      (libsource (lib "PROJE") (part "RES 22Ω 1206"))
    )
    (comp (ref "R16")
      (value "22Ω")
      (footprint "R-1206W")
      (description "CRG1206 1% 22R")
      (fields (field (name "MP") "1623463-1"))
      (libsource (lib "PROJE") (part "RES 22Ω 1206"))
    )
    (comp (ref "R17")
      (value "22Ω")
      (footprint "R-1206W")
      (description "CRG1206 1% 22R")
      (fields (field (name "MP") "1623463-1"))
      (libsource (lib "PROJE") (part "RES 22Ω 1206"))
    )
    (comp (ref "R18")
      (value "22Ω")
      (footprint "R-1206W")
      (description "CRG1206 1% 22R")
      (fields (field (name "MP") "1623463-1"))
      (libsource (lib "PROJE") (part "RES 22Ω 1206"))
    )
    (comp (ref "R19")
      (value "22Ω")
      (footprint "R-1206W")
      (description "CRG1206 1% 22R")
      (fields (field (name "MP") "1623463-1"))
      (libsource (lib "PROJE") (part "RES 22Ω 1206"))
    )
    (comp (ref "R20")
      (value "22Ω")
      (footprint "R-1206W")
      (description "CRG1206 1% 22R")
      (fields (field (name "MP") "1623463-1"))
      (libsource (lib "PROJE") (part "RES 22Ω 1206"))
    )
    (comp (ref "R21")
      (value "22Ω")
      (footprint "R-1206W")
      (description "CRG1206 1% 22R")
      (fields (field (name "MP") "1623463-1"))
      (libsource (lib "PROJE") (part "RES 22Ω 1206"))
    )
    (comp (ref "R23")
      (value "RES SMD 10K OHM 1% 1/8W 0805")
      (footprint "R-0805W")
      (description "10 kOhms ±1% 0.125W, 1/8W Chip Resistor 0805 (2012 Metric) Moisture Resistant Thick Film")
      (fields (field (name "DEGER") "10K"))
      (libsource (lib "PROJE") (part "10K 0805"))
    )
    (comp (ref "R24")
      (value "RES SMD 10K OHM 1% 1/8W 0805")
      (footprint "R-0805W")
      (description "10 kOhms ±1% 0.125W, 1/8W Chip Resistor 0805 (2012 Metric) Moisture Resistant Thick Film")
      (fields (field (name "DEGER") "10K"))
      (libsource (lib "PROJE") (part "10K 0805"))
    )
    (comp (ref "R25")
      (value "RES SMD 10K OHM 1% 1/8W 0805")
      (footprint "R-0805W")
      (description "10 kOhms ±1% 0.125W, 1/8W Chip Resistor 0805 (2012 Metric) Moisture Resistant Thick Film")
      (fields (field (name "DEGER") "10K"))
      (libsource (lib "PROJE") (part "10K 0805"))
    )
    (comp (ref "R26")
      (value "RES SMD 10K OHM 1% 1/8W 0805")
      (footprint "R-0805W")
      (description "10 kOhms ±1% 0.125W, 1/8W Chip Resistor 0805 (2012 Metric) Moisture Resistant Thick Film")
      (fields (field (name "DEGER") "10K"))
      (libsource (lib "PROJE") (part "10K 0805"))
    )
    (comp (ref "R27")
      (value "RES SMD 10K OHM 1% 1/8W 0805")
      (footprint "R-0805W")
      (description "10 kOhms ±1% 0.125W, 1/8W Chip Resistor 0805 (2012 Metric) Moisture Resistant Thick Film")
      (fields (field (name "DEGER") "10K"))
      (libsource (lib "PROJE") (part "10K 0805"))
    )
    (comp (ref "R28")
      (value "RES SMD 10K OHM 1% 1/8W 0805")
      (footprint "R-0805W")
      (description "10 kOhms ±1% 0.125W, 1/8W Chip Resistor 0805 (2012 Metric) Moisture Resistant Thick Film")
      (fields (field (name "DEGER") "10K"))
      (libsource (lib "PROJE") (part "10K 0805"))
    )
    (comp (ref "R29")
      (value "RES SMD 10K OHM 1% 1/8W 0805")
      (footprint "R-0805W")
      (description "10 kOhms ±1% 0.125W, 1/8W Chip Resistor 0805 (2012 Metric) Moisture Resistant Thick Film")
      (fields (field (name "DEGER") "10K"))
      (libsource (lib "PROJE") (part "10K 0805"))
    )
    (comp (ref "R30") (value "1") (footprint "R-2512W") (libsource (lib "PROJE") (part "0207 melf")))
    (comp (ref "R31") (value "1") (footprint "R-2512W") (libsource (lib "PROJE") (part "0207 melf")))
    (comp (ref "R32")
      (value "22Ω")
      (footprint "R-1206W")
      (description "CRG1206 1% 22R")
      (fields (field (name "MP") "1623463-1"))
      (libsource (lib "PROJE") (part "RES 22Ω 1206"))
    )
    (comp (ref "R33")
      (value "22Ω")
      (footprint "R-1206W")
      (description "CRG1206 1% 22R")
      (fields (field (name "MP") "1623463-1"))
      (libsource (lib "PROJE") (part "RES 22Ω 1206"))
    )
    (comp (ref "R34")
      (value "RES SMD 10K OHM 1% 1/8W 0805")
      (footprint "R-0805W")
      (description "10 kOhms ±1% 0.125W, 1/8W Chip Resistor 0805 (2012 Metric) Moisture Resistant Thick Film")
      (fields (field (name "DEGER") "10K"))
      (libsource (lib "PROJE") (part "10K 0805"))
    )
    (comp (ref "R35")
      (value "22Ω")
      (footprint "R-1206W")
      (description "CRG1206 1% 22R")
      (fields (field (name "MP") "1623463-1"))
      (libsource (lib "PROJE") (part "RES 22Ω 1206"))
    )
    (comp (ref "R36")
      (value "RES SMD 10K OHM 1% 1/8W 0805")
      (footprint "R-0805W")
      (description "10 kOhms ±1% 0.125W, 1/8W Chip Resistor 0805 (2012 Metric) Moisture Resistant Thick Film")
      (fields (field (name "DEGER") "10K"))
      (libsource (lib "PROJE") (part "10K 0805"))
    )
    (comp (ref "R37")
      (value "22Ω")
      (footprint "R-1206W")
      (description "CRG1206 1% 22R")
      (fields (field (name "MP") "1623463-1"))
      (libsource (lib "PROJE") (part "RES 22Ω 1206"))
    )
    (comp (ref "R38")
      (value "RES SMD 10K OHM 1% 1/8W 0805")
      (footprint "R-0805W")
      (description "10 kOhms ±1% 0.125W, 1/8W Chip Resistor 0805 (2012 Metric) Moisture Resistant Thick Film")
      (fields (field (name "DEGER") "10K"))
      (libsource (lib "PROJE") (part "10K 0805"))
    )
    (comp (ref "R39")
      (value "22Ω")
      (footprint "R-1206W")
      (description "CRG1206 1% 22R")
      (fields (field (name "MP") "1623463-1"))
      (libsource (lib "PROJE") (part "RES 22Ω 1206"))
    )
    (comp (ref "R40")
      (value "RES SMD 10K OHM 1% 1/8W 0805")
      (footprint "R-0805W")
      (description "10 kOhms ±1% 0.125W, 1/8W Chip Resistor 0805 (2012 Metric) Moisture Resistant Thick Film")
      (fields (field (name "DEGER") "10K"))
      (libsource (lib "PROJE") (part "10K 0805"))
    )
    (comp (ref "R41")
      (value "22Ω")
      (footprint "R-1206W")
      (description "CRG1206 1% 22R")
      (fields (field (name "MP") "1623463-1"))
      (libsource (lib "PROJE") (part "RES 22Ω 1206"))
    )
    (comp (ref "R42")
      (value "RES SMD 10K OHM 1% 1/8W 0805")
      (footprint "R-0805W")
      (description "10 kOhms ±1% 0.125W, 1/8W Chip Resistor 0805 (2012 Metric) Moisture Resistant Thick Film")
      (fields (field (name "DEGER") "10K"))
      (libsource (lib "PROJE") (part "10K 0805"))
    )
    (comp (ref "R43")
      (value "22Ω")
      (footprint "R-1206W")
      (description "CRG1206 1% 22R")
      (fields (field (name "MP") "1623463-1"))
      (libsource (lib "PROJE") (part "RES 22Ω 1206"))
    )
    (comp (ref "R44")
      (value "RES SMD 10K OHM 1% 1/8W 0805")
      (footprint "R-0805W")
      (description "10 kOhms ±1% 0.125W, 1/8W Chip Resistor 0805 (2012 Metric) Moisture Resistant Thick Film")
      (fields (field (name "DEGER") "10K"))
      (libsource (lib "PROJE") (part "10K 0805"))
    )
    (comp (ref "R45")
      (value "RES SMD 10K OHM 1% 1/8W 0805")
      (footprint "R-0805W")
      (description "10 kOhms ±1% 0.125W, 1/8W Chip Resistor 0805 (2012 Metric) Moisture Resistant Thick Film")
      (fields (field (name "DEGER") "10K"))
      (libsource (lib "PROJE") (part "10K 0805"))
    )
    (comp (ref "R46")
      (value "22Ω")
      (footprint "R-1206W")
      (description "CRG1206 1% 22R")
      (fields (field (name "MP") "1623463-1"))
      (libsource (lib "PROJE") (part "RES 22Ω 1206"))
    )
    (comp (ref "R47")
      (value "22Ω")
      (footprint "R-1206W")
      (description "CRG1206 1% 22R")
      (fields (field (name "MP") "1623463-1"))
      (libsource (lib "PROJE") (part "RES 22Ω 1206"))
    )
    (comp (ref "R48")
      (value "22Ω")
      (footprint "R-1206W")
      (description "CRG1206 1% 22R")
      (fields (field (name "MP") "1623463-1"))
      (libsource (lib "PROJE") (part "RES 22Ω 1206"))
    )
    (comp (ref "R49")
      (value "22Ω")
      (footprint "R-1206W")
      (description "CRG1206 1% 22R")
      (fields (field (name "MP") "1623463-1"))
      (libsource (lib "PROJE") (part "RES 22Ω 1206"))
    )
    (comp (ref "R50")
      (value "22Ω")
      (footprint "R-1206W")
      (description "CRG1206 1% 22R")
      (fields (field (name "MP") "1623463-1"))
      (libsource (lib "PROJE") (part "RES 22Ω 1206"))
    )
    (comp (ref "R51")
      (value "22Ω")
      (footprint "R-1206W")
      (description "CRG1206 1% 22R")
      (fields (field (name "MP") "1623463-1"))
      (libsource (lib "PROJE") (part "RES 22Ω 1206"))
    )
    (comp (ref "R52")
      (value "22Ω")
      (footprint "R-1206W")
      (description "CRG1206 1% 22R")
      (fields (field (name "MP") "1623463-1"))
      (libsource (lib "PROJE") (part "RES 22Ω 1206"))
    )
    (comp (ref "R54")
      (value "RES SMD 10K OHM 1% 1/8W 0805")
      (footprint "R-0805W")
      (description "10 kOhms ±1% 0.125W, 1/8W Chip Resistor 0805 (2012 Metric) Moisture Resistant Thick Film")
      (fields (field (name "DEGER") "10K"))
      (libsource (lib "PROJE") (part "10K 0805"))
    )
    (comp (ref "R55")
      (value "RES SMD 10K OHM 1% 1/8W 0805")
      (footprint "R-0805W")
      (description "10 kOhms ±1% 0.125W, 1/8W Chip Resistor 0805 (2012 Metric) Moisture Resistant Thick Film")
      (fields (field (name "DEGER") "10K"))
      (libsource (lib "PROJE") (part "10K 0805"))
    )
    (comp (ref "R56")
      (value "RES SMD 10K OHM 1% 1/8W 0805")
      (footprint "R-0805W")
      (description "10 kOhms ±1% 0.125W, 1/8W Chip Resistor 0805 (2012 Metric) Moisture Resistant Thick Film")
      (fields (field (name "DEGER") "10K"))
      (libsource (lib "PROJE") (part "10K 0805"))
    )
    (comp (ref "R57")
      (value "RES SMD 10K OHM 1% 1/8W 0805")
      (footprint "R-0805W")
      (description "10 kOhms ±1% 0.125W, 1/8W Chip Resistor 0805 (2012 Metric) Moisture Resistant Thick Film")
      (fields (field (name "DEGER") "10K"))
      (libsource (lib "PROJE") (part "10K 0805"))
    )
    (comp (ref "R58")
      (value "RES SMD 10K OHM 1% 1/8W 0805")
      (footprint "R-0805W")
      (description "10 kOhms ±1% 0.125W, 1/8W Chip Resistor 0805 (2012 Metric) Moisture Resistant Thick Film")
      (fields (field (name "DEGER") "10K"))
      (libsource (lib "PROJE") (part "10K 0805"))
    )
    (comp (ref "R59")
      (value "RES SMD 10K OHM 1% 1/8W 0805")
      (footprint "R-0805W")
      (description "10 kOhms ±1% 0.125W, 1/8W Chip Resistor 0805 (2012 Metric) Moisture Resistant Thick Film")
      (fields (field (name "DEGER") "10K"))
      (libsource (lib "PROJE") (part "10K 0805"))
    )
    (comp (ref "R60")
      (value "RES SMD 10K OHM 1% 1/8W 0805")
      (footprint "R-0805W")
      (description "10 kOhms ±1% 0.125W, 1/8W Chip Resistor 0805 (2012 Metric) Moisture Resistant Thick Film")
      (fields (field (name "DEGER") "10K"))
      (libsource (lib "PROJE") (part "10K 0805"))
    )
    (comp (ref "R61") (value "1") (footprint "R-2512W") (libsource (lib "PROJE") (part "0207 melf")))
    (comp (ref "R62") (value "1") (footprint "R-2512W") (libsource (lib "PROJE") (part "0207 melf")))
    (comp (ref "R63")
      (value "22Ω")
      (footprint "R-1206W")
      (description "CRG1206 1% 22R")
      (fields (field (name "MP") "1623463-1"))
      (libsource (lib "PROJE") (part "RES 22Ω 1206"))
    )
    (comp (ref "R64")
      (value "22Ω")
      (footprint "R-1206W")
      (description "CRG1206 1% 22R")
      (fields (field (name "MP") "1623463-1"))
      (libsource (lib "PROJE") (part "RES 22Ω 1206"))
    )
    (comp (ref "R65")
      (value "RES SMD 10K OHM 1% 1/8W 0805")
      (footprint "R-0805W")
      (description "10 kOhms ±1% 0.125W, 1/8W Chip Resistor 0805 (2012 Metric) Moisture Resistant Thick Film")
      (fields (field (name "DEGER") "10K"))
      (libsource (lib "PROJE") (part "10K 0805"))
    )
    (comp (ref "R66")
      (value "22Ω")
      (footprint "R-1206W")
      (description "CRG1206 1% 22R")
      (fields (field (name "MP") "1623463-1"))
      (libsource (lib "PROJE") (part "RES 22Ω 1206"))
    )
    (comp (ref "R67")
      (value "RES SMD 10K OHM 1% 1/8W 0805")
      (footprint "R-0805W")
      (description "10 kOhms ±1% 0.125W, 1/8W Chip Resistor 0805 (2012 Metric) Moisture Resistant Thick Film")
      (fields (field (name "DEGER") "10K"))
      (libsource (lib "PROJE") (part "10K 0805"))
    )
    (comp (ref "R68")
      (value "22Ω")
      (footprint "R-1206W")
      (description "CRG1206 1% 22R")
      (fields (field (name "MP") "1623463-1"))
      (libsource (lib "PROJE") (part "RES 22Ω 1206"))
    )
    (comp (ref "R69")
      (value "RES SMD 10K OHM 1% 1/8W 0805")
      (footprint "R-0805W")
      (description "10 kOhms ±1% 0.125W, 1/8W Chip Resistor 0805 (2012 Metric) Moisture Resistant Thick Film")
      (fields (field (name "DEGER") "10K"))
      (libsource (lib "PROJE") (part "10K 0805"))
    )
    (comp (ref "R70")
      (value "22Ω")
      (footprint "R-1206W")
      (description "CRG1206 1% 22R")
      (fields (field (name "MP") "1623463-1"))
      (libsource (lib "PROJE") (part "RES 22Ω 1206"))
    )
    (comp (ref "R71")
      (value "RES SMD 10K OHM 1% 1/8W 0805")
      (footprint "R-0805W")
      (description "10 kOhms ±1% 0.125W, 1/8W Chip Resistor 0805 (2012 Metric) Moisture Resistant Thick Film")
      (fields (field (name "DEGER") "10K"))
      (libsource (lib "PROJE") (part "10K 0805"))
    )
    (comp (ref "R72")
      (value "22Ω")
      (footprint "R-1206W")
      (description "CRG1206 1% 22R")
      (fields (field (name "MP") "1623463-1"))
      (libsource (lib "PROJE") (part "RES 22Ω 1206"))
    )
    (comp (ref "R73")
      (value "RES SMD 10K OHM 1% 1/8W 0805")
      (footprint "R-0805W")
      (description "10 kOhms ±1% 0.125W, 1/8W Chip Resistor 0805 (2012 Metric) Moisture Resistant Thick Film")
      (fields (field (name "DEGER") "10K"))
      (libsource (lib "PROJE") (part "10K 0805"))
    )
    (comp (ref "R74")
      (value "22Ω")
      (footprint "R-1206W")
      (description "CRG1206 1% 22R")
      (fields (field (name "MP") "1623463-1"))
      (libsource (lib "PROJE") (part "RES 22Ω 1206"))
    )
    (comp (ref "R75")
      (value "RES SMD 10K OHM 1% 1/8W 0805")
      (footprint "R-0805W")
      (description "10 kOhms ±1% 0.125W, 1/8W Chip Resistor 0805 (2012 Metric) Moisture Resistant Thick Film")
      (fields (field (name "DEGER") "10K"))
      (libsource (lib "PROJE") (part "10K 0805"))
    )
    (comp (ref "R76")
      (value "RES SMD 10K OHM 1% 1/8W 0805")
      (footprint "R-0805W")
      (description "10 kOhms ±1% 0.125W, 1/8W Chip Resistor 0805 (2012 Metric) Moisture Resistant Thick Film")
      (fields (field (name "DEGER") "10K"))
      (libsource (lib "PROJE") (part "10K 0805"))
    )
    (comp (ref "R77")
      (value "22Ω")
      (footprint "R-1206W")
      (description "CRG1206 1% 22R")
      (fields (field (name "MP") "1623463-1"))
      (libsource (lib "PROJE") (part "RES 22Ω 1206"))
    )
    (comp (ref "R78")
      (value "22Ω")
      (footprint "R-1206W")
      (description "CRG1206 1% 22R")
      (fields (field (name "MP") "1623463-1"))
      (libsource (lib "PROJE") (part "RES 22Ω 1206"))
    )
    (comp (ref "R79")
      (value "22Ω")
      (footprint "R-1206W")
      (description "CRG1206 1% 22R")
      (fields (field (name "MP") "1623463-1"))
      (libsource (lib "PROJE") (part "RES 22Ω 1206"))
    )
    (comp (ref "R80")
      (value "22Ω")
      (footprint "R-1206W")
      (description "CRG1206 1% 22R")
      (fields (field (name "MP") "1623463-1"))
      (libsource (lib "PROJE") (part "RES 22Ω 1206"))
    )
    (comp (ref "R81")
      (value "22Ω")
      (footprint "R-1206W")
      (description "CRG1206 1% 22R")
      (fields (field (name "MP") "1623463-1"))
      (libsource (lib "PROJE") (part "RES 22Ω 1206"))
    )
    (comp (ref "R82")
      (value "22Ω")
      (footprint "R-1206W")
      (description "CRG1206 1% 22R")
      (fields (field (name "MP") "1623463-1"))
      (libsource (lib "PROJE") (part "RES 22Ω 1206"))
    )
    (comp (ref "R83")
      (value "22Ω")
      (footprint "R-1206W")
      (description "CRG1206 1% 22R")
      (fields (field (name "MP") "1623463-1"))
      (libsource (lib "PROJE") (part "RES 22Ω 1206"))
    )
    (comp (ref "R85")
      (value "RES SMD 10K OHM 1% 1/8W 0805")
      (footprint "R-0805W")
      (description "10 kOhms ±1% 0.125W, 1/8W Chip Resistor 0805 (2012 Metric) Moisture Resistant Thick Film")
      (fields (field (name "DEGER") "10K"))
      (libsource (lib "PROJE") (part "10K 0805"))
    )
    (comp (ref "R86")
      (value "RES SMD 10K OHM 1% 1/8W 0805")
      (footprint "R-0805W")
      (description "10 kOhms ±1% 0.125W, 1/8W Chip Resistor 0805 (2012 Metric) Moisture Resistant Thick Film")
      (fields (field (name "DEGER") "10K"))
      (libsource (lib "PROJE") (part "10K 0805"))
    )
    (comp (ref "R87")
      (value "RES SMD 10K OHM 1% 1/8W 0805")
      (footprint "R-0805W")
      (description "10 kOhms ±1% 0.125W, 1/8W Chip Resistor 0805 (2012 Metric) Moisture Resistant Thick Film")
      (fields (field (name "DEGER") "10K"))
      (libsource (lib "PROJE") (part "10K 0805"))
    )
    (comp (ref "R88")
      (value "RES SMD 10K OHM 1% 1/8W 0805")
      (footprint "R-0805W")
      (description "10 kOhms ±1% 0.125W, 1/8W Chip Resistor 0805 (2012 Metric) Moisture Resistant Thick Film")
      (fields (field (name "DEGER") "10K"))
      (libsource (lib "PROJE") (part "10K 0805"))
    )
    (comp (ref "R89")
      (value "RES SMD 10K OHM 1% 1/8W 0805")
      (footprint "R-0805W")
      (description "10 kOhms ±1% 0.125W, 1/8W Chip Resistor 0805 (2012 Metric) Moisture Resistant Thick Film")
      (fields (field (name "DEGER") "10K"))
      (libsource (lib "PROJE") (part "10K 0805"))
    )
    (comp (ref "R90")
      (value "RES SMD 10K OHM 1% 1/8W 0805")
      (footprint "R-0805W")
      (description "10 kOhms ±1% 0.125W, 1/8W Chip Resistor 0805 (2012 Metric) Moisture Resistant Thick Film")
      (fields (field (name "DEGER") "10K"))
      (libsource (lib "PROJE") (part "10K 0805"))
    )
    (comp (ref "R91")
      (value "RES SMD 10K OHM 1% 1/8W 0805")
      (footprint "R-0805W")
      (description "10 kOhms ±1% 0.125W, 1/8W Chip Resistor 0805 (2012 Metric) Moisture Resistant Thick Film")
      (fields (field (name "DEGER") "10K"))
      (libsource (lib "PROJE") (part "10K 0805"))
    )
    (comp (ref "R92") (value "1") (footprint "R-2512W") (libsource (lib "PROJE") (part "0207 melf")))
    (comp (ref "R93") (value "1") (footprint "R-2512W") (libsource (lib "PROJE") (part "0207 melf")))
    (comp (ref "R114") (value "1") (footprint "R-2512W") (libsource (lib "PROJE") (part "0207 melf")))
    (comp (ref "R115") (value "1") (footprint "R-2512W") (libsource (lib "PROJE") (part "0207 melf")))
    (comp (ref "R116") (value "1") (footprint "R-2512W") (libsource (lib "PROJE") (part "0207 melf")))
    (comp (ref "R117") (value "1") (footprint "R-2512W") (libsource (lib "PROJE") (part "0207 melf")))
    (comp (ref "R118") (value "1") (footprint "R-2512W") (libsource (lib "PROJE") (part "0207 melf")))
    (comp (ref "R119") (value "1") (footprint "R-2512W") (libsource (lib "PROJE") (part "0207 melf")))
    (comp (ref "R120") (value "1") (footprint "R-2512W") (libsource (lib "PROJE") (part "0207 melf")))
    (comp (ref "R121") (value "1") (footprint "R-2512W") (libsource (lib "PROJE") (part "0207 melf")))
    (comp (ref "R122") (value "1") (footprint "R-2512W") (libsource (lib "PROJE") (part "0207 melf")))
    (comp (ref "R123") (value "1") (footprint "R-2512W") (libsource (lib "PROJE") (part "0207 melf")))
    (comp (ref "R124") (value "1") (footprint "R-2512W") (libsource (lib "PROJE") (part "0207 melf")))
    (comp (ref "R125") (value "1") (footprint "R-2512W") (libsource (lib "PROJE") (part "0207 melf")))
    (comp (ref "R155")
      (value "11Ω")
      (footprint "R-1206W")
      (description "CRG1206 1% 11R")
      (fields (field (name "MP") "1623463-1"))
      (libsource (lib "PROJE") (part "RES 11Ω 1206"))
    )
    (comp (ref "R156")
      (value "11Ω")
      (footprint "R-1206W")
      (description "CRG1206 1% 11R")
      (fields (field (name "MP") "1623463-1"))
      (libsource (lib "PROJE") (part "RES 11Ω 1206"))
    )
    (comp (ref "R157")
      (value "11Ω")
      (footprint "R-1206W")
      (description "CRG1206 1% 11R")
      (fields (field (name "MP") "1623463-1"))
      (libsource (lib "PROJE") (part "RES 11Ω 1206"))
    )
    (comp (ref "R158")
      (value "11Ω")
      (footprint "R-1206W")
      (description "CRG1206 1% 11R")
      (fields (field (name "MP") "1623463-1"))
      (libsource (lib "PROJE") (part "RES 11Ω 1206"))
    )
    (comp (ref "R159")
      (value "11Ω")
      (footprint "R-1206W")
      (description "CRG1206 1% 11R")
      (fields (field (name "MP") "1623463-1"))
      (libsource (lib "PROJE") (part "RES 11Ω 1206"))
    )
    (comp (ref "R160")
      (value "11Ω")
      (footprint "R-1206W")
      (description "CRG1206 1% 11R")
      (fields (field (name "MP") "1623463-1"))
      (libsource (lib "PROJE") (part "RES 11Ω 1206"))
    )
    (comp (ref "R161")
      (value "11Ω")
      (footprint "R-1206W")
      (description "CRG1206 1% 11R")
      (fields (field (name "MP") "1623463-1"))
      (libsource (lib "PROJE") (part "RES 11Ω 1206"))
    )
    (comp (ref "R162")
      (value "11Ω")
      (footprint "R-1206W")
      (description "CRG1206 1% 11R")
      (fields (field (name "MP") "1623463-1"))
      (libsource (lib "PROJE") (part "RES 11Ω 1206"))
    )
    (comp (ref "R163")
      (value "11Ω")
      (footprint "R-1206W")
      (description "CRG1206 1% 11R")
      (fields (field (name "MP") "1623463-1"))
      (libsource (lib "PROJE") (part "RES 11Ω 1206"))
    )
    (comp (ref "R164")
      (value "11Ω")
      (footprint "R-1206W")
      (description "CRG1206 1% 11R")
      (fields (field (name "MP") "1623463-1"))
      (libsource (lib "PROJE") (part "RES 11Ω 1206"))
    )
    (comp (ref "R165")
      (value "11Ω")
      (footprint "R-1206W")
      (description "CRG1206 1% 11R")
      (fields (field (name "MP") "1623463-1"))
      (libsource (lib "PROJE") (part "RES 11Ω 1206"))
    )
    (comp (ref "R166")
      (value "11Ω")
      (footprint "R-1206W")
      (description "CRG1206 1% 11R")
      (fields (field (name "MP") "1623463-1"))
      (libsource (lib "PROJE") (part "RES 11Ω 1206"))
    )
    (comp (ref "R167")
      (value "11Ω")
      (footprint "R-1206W")
      (description "CRG1206 1% 11R")
      (fields (field (name "MP") "1623463-1"))
      (libsource (lib "PROJE") (part "RES 11Ω 1206"))
    )
    (comp (ref "R168")
      (value "11Ω")
      (footprint "R-1206W")
      (description "CRG1206 1% 11R")
      (fields (field (name "MP") "1623463-1"))
      (libsource (lib "PROJE") (part "RES 11Ω 1206"))
    )
    (comp (ref "R169")
      (value "11Ω")
      (footprint "R-1206W")
      (description "CRG1206 1% 11R")
      (fields (field (name "MP") "1623463-1"))
      (libsource (lib "PROJE") (part "RES 11Ω 1206"))
    )
    (comp (ref "R170")
      (value "11Ω")
      (footprint "R-1206W")
      (description "CRG1206 1% 11R")
      (fields (field (name "MP") "1623463-1"))
      (libsource (lib "PROJE") (part "RES 11Ω 1206"))
    )
    (comp (ref "R171")
      (value "11Ω")
      (footprint "R-1206W")
      (description "CRG1206 1% 11R")
      (fields (field (name "MP") "1623463-1"))
      (libsource (lib "PROJE") (part "RES 11Ω 1206"))
    )
    (comp (ref "R172")
      (value "11Ω")
      (footprint "R-1206W")
      (description "CRG1206 1% 11R")
      (fields (field (name "MP") "1623463-1"))
      (libsource (lib "PROJE") (part "RES 11Ω 1206"))
    )
    (comp (ref "R173")
      (value "11Ω")
      (footprint "R-1206W")
      (description "CRG1206 1% 11R")
      (fields (field (name "MP") "1623463-1"))
      (libsource (lib "PROJE") (part "RES 11Ω 1206"))
    )
    (comp (ref "R174")
      (value "11Ω")
      (footprint "R-1206W")
      (description "CRG1206 1% 11R")
      (fields (field (name "MP") "1623463-1"))
      (libsource (lib "PROJE") (part "RES 11Ω 1206"))
    )
    (comp (ref "R175")
      (value "11Ω")
      (footprint "R-1206W")
      (description "CRG1206 1% 11R")
      (fields (field (name "MP") "1623463-1"))
      (libsource (lib "PROJE") (part "RES 11Ω 1206"))
    )
    (comp (ref "R176")
      (value "11Ω")
      (footprint "R-1206W")
      (description "CRG1206 1% 11R")
      (fields (field (name "MP") "1623463-1"))
      (libsource (lib "PROJE") (part "RES 11Ω 1206"))
    )
    (comp (ref "R177")
      (value "11Ω")
      (footprint "R-1206W")
      (description "CRG1206 1% 11R")
      (fields (field (name "MP") "1623463-1"))
      (libsource (lib "PROJE") (part "RES 11Ω 1206"))
    )
    (comp (ref "R178")
      (value "11Ω")
      (footprint "R-1206W")
      (description "CRG1206 1% 11R")
      (fields (field (name "MP") "1623463-1"))
      (libsource (lib "PROJE") (part "RES 11Ω 1206"))
    )
    (comp (ref "R179")
      (value "11Ω")
      (footprint "R-1206W")
      (description "CRG1206 1% 11R")
      (fields (field (name "MP") "1623463-1"))
      (libsource (lib "PROJE") (part "RES 11Ω 1206"))
    )
    (comp (ref "R180")
      (value "11Ω")
      (footprint "R-1206W")
      (description "CRG1206 1% 11R")
      (fields (field (name "MP") "1623463-1"))
      (libsource (lib "PROJE") (part "RES 11Ω 1206"))
    )
    (comp (ref "R181")
      (value "11Ω")
      (footprint "R-1206W")
      (description "CRG1206 1% 11R")
      (fields (field (name "MP") "1623463-1"))
      (libsource (lib "PROJE") (part "RES 11Ω 1206"))
    )
    (comp (ref "R182")
      (value "11Ω")
      (footprint "R-1206W")
      (description "CRG1206 1% 11R")
      (fields (field (name "MP") "1623463-1"))
      (libsource (lib "PROJE") (part "RES 11Ω 1206"))
    )
    (comp (ref "R183")
      (value "11Ω")
      (footprint "R-1206W")
      (description "CRG1206 1% 11R")
      (fields (field (name "MP") "1623463-1"))
      (libsource (lib "PROJE") (part "RES 11Ω 1206"))
    )
    (comp (ref "R184")
      (value "11Ω")
      (footprint "R-1206W")
      (description "CRG1206 1% 11R")
      (fields (field (name "MP") "1623463-1"))
      (libsource (lib "PROJE") (part "RES 11Ω 1206"))
    )
    (comp (ref "R185")
      (value "11Ω")
      (footprint "R-1206W")
      (description "CRG1206 1% 11R")
      (fields (field (name "MP") "1623463-1"))
      (libsource (lib "PROJE") (part "RES 11Ω 1206"))
    )
    (comp (ref "R186")
      (value "11Ω")
      (footprint "R-1206W")
      (description "CRG1206 1% 11R")
      (fields (field (name "MP") "1623463-1"))
      (libsource (lib "PROJE") (part "RES 11Ω 1206"))
    )
    (comp (ref "R187")
      (value "11Ω")
      (footprint "R-1206W")
      (description "CRG1206 1% 11R")
      (fields (field (name "MP") "1623463-1"))
      (libsource (lib "PROJE") (part "RES 11Ω 1206"))
    )
    (comp (ref "R188")
      (value "11Ω")
      (footprint "R-1206W")
      (description "CRG1206 1% 11R")
      (fields (field (name "MP") "1623463-1"))
      (libsource (lib "PROJE") (part "RES 11Ω 1206"))
    )
    (comp (ref "R189")
      (value "11Ω")
      (footprint "R-1206W")
      (description "CRG1206 1% 11R")
      (fields (field (name "MP") "1623463-1"))
      (libsource (lib "PROJE") (part "RES 11Ω 1206"))
    )
    (comp (ref "R190")
      (value "11Ω")
      (footprint "R-1206W")
      (description "CRG1206 1% 11R")
      (fields (field (name "MP") "1623463-1"))
      (libsource (lib "PROJE") (part "RES 11Ω 1206"))
    )
    (comp (ref "R191")
      (value "11Ω")
      (footprint "R-1206W")
      (description "CRG1206 1% 11R")
      (fields (field (name "MP") "1623463-1"))
      (libsource (lib "PROJE") (part "RES 11Ω 1206"))
    )
    (comp (ref "R192")
      (value "11Ω")
      (footprint "R-1206W")
      (description "CRG1206 1% 11R")
      (fields (field (name "MP") "1623463-1"))
      (libsource (lib "PROJE") (part "RES 11Ω 1206"))
    )
    (comp (ref "R193")
      (value "11Ω")
      (footprint "R-1206W")
      (description "CRG1206 1% 11R")
      (fields (field (name "MP") "1623463-1"))
      (libsource (lib "PROJE") (part "RES 11Ω 1206"))
    )
    (comp (ref "R194")
      (value "11Ω")
      (footprint "R-1206W")
      (description "CRG1206 1% 11R")
      (fields (field (name "MP") "1623463-1"))
      (libsource (lib "PROJE") (part "RES 11Ω 1206"))
    )
    (comp (ref "R195")
      (value "11Ω")
      (footprint "R-1206W")
      (description "CRG1206 1% 11R")
      (fields (field (name "MP") "1623463-1"))
      (libsource (lib "PROJE") (part "RES 11Ω 1206"))
    )
    (comp (ref "R196")
      (value "11Ω")
      (footprint "R-1206W")
      (description "CRG1206 1% 11R")
      (fields (field (name "MP") "1623463-1"))
      (libsource (lib "PROJE") (part "RES 11Ω 1206"))
    )
    (comp (ref "T1")
      (value "TCon")
      (footprint "connectorout")
      (libsource (lib "PROJE") (part "Terminal Connector"))
    )
    (comp (ref "T2")
      (value "TCon")
      (footprint "connectorout")
      (libsource (lib "PROJE") (part "Terminal Connector"))
    )
    (comp (ref "T3")
      (value "TCon")
      (footprint "connectorout")
      (libsource (lib "PROJE") (part "Terminal Connector"))
    )
    (comp (ref "T4")
      (value "TCon")
      (footprint "connectorout")
      (libsource (lib "PROJE") (part "Terminal Connector"))
    )
    (comp (ref "T5")
      (value "TCon")
      (footprint "connectorout")
      (libsource (lib "PROJE") (part "Terminal Connector"))
    )
    (comp (ref "T6")
      (value "TCon")
      (footprint "connectorout")
      (libsource (lib "PROJE") (part "Terminal Connector"))
    )
    (comp (ref "T7")
      (value "TCon")
      (footprint "connectorout")
      (libsource (lib "PROJE") (part "Terminal Connector"))
    )
    (comp (ref "T8")
      (value "TCon")
      (footprint "connectorout")
      (libsource (lib "PROJE") (part "Terminal Connector"))
    )
    (comp (ref "T9")
      (value "TCon")
      (footprint "connectorout")
      (libsource (lib "PROJE") (part "Terminal Connector"))
    )
    (comp (ref "T10")
      (value "TCon")
      (footprint "connectorout")
      (libsource (lib "PROJE") (part "Terminal Connector"))
    )
    (comp (ref "T11")
      (value "TCon")
      (footprint "connectorout")
      (libsource (lib "PROJE") (part "Terminal Connector"))
    )
    (comp (ref "T12")
      (value "TCon")
      (footprint "connectorout")
      (libsource (lib "PROJE") (part "Terminal Connector"))
    )
    (comp (ref "T13")
      (value "TCon")
      (footprint "connectorout")
      (libsource (lib "PROJE") (part "Terminal Connector"))
    )
    (comp (ref "T14")
      (value "TCon")
      (footprint "connectorout")
      (libsource (lib "PROJE") (part "Terminal Connector"))
    )
    (comp (ref "T15")
      (value "TCon")
      (footprint "connectorout")
      (libsource (lib "PROJE") (part "Terminal Connector"))
    )
    (comp (ref "T16")
      (value "TCon")
      (footprint "connectorout")
      (libsource (lib "PROJE") (part "Terminal Connector"))
    )
    (comp (ref "T17")
      (value "TCon")
      (footprint "connectorout")
      (libsource (lib "PROJE") (part "Terminal Connector"))
    )
    (comp (ref "T18")
      (value "TCon")
      (footprint "connectorout")
      (libsource (lib "PROJE") (part "Terminal Connector"))
    )
    (comp (ref "T19")
      (value "TCon")
      (footprint "connectorout")
      (libsource (lib "PROJE") (part "Terminal Connector"))
    )
    (comp (ref "T20")
      (value "TCon")
      (footprint "connectorout")
      (libsource (lib "PROJE") (part "Terminal Connector"))
    )
    (comp (ref "T21")
      (value "TCon")
      (footprint "connectorout")
      (libsource (lib "PROJE") (part "Terminal Connector"))
    )
  )
  (nets
    (net (code "1") (name "+48V") (class "Default")
      (node (ref "C1") (pin "2") (pinfunction "2_2") (pintype "passive"))
      (node (ref "C18") (pin "2") (pinfunction "2_2") (pintype "passive"))
      (node (ref "C19") (pin "2") (pinfunction "2_2") (pintype "passive"))
      (node (ref "C2") (pin "2") (pinfunction "2_2") (pintype "passive"))
      (node (ref "C35") (pin "2") (pinfunction "2_2") (pintype "passive"))
      (node (ref "C36") (pin "2") (pinfunction "2_2") (pintype "passive"))
      (node (ref "Q1") (pin "3") (pinfunction "3_3") (pintype "passive"))
      (node (ref "Q15") (pin "3") (pinfunction "3_3") (pintype "passive"))
      (node (ref "Q16") (pin "3") (pinfunction "3_3") (pintype "passive"))
      (node (ref "Q17") (pin "3") (pinfunction "3_3") (pintype "passive"))
      (node (ref "Q18") (pin "3") (pinfunction "3_3") (pintype "passive"))
      (node (ref "Q19") (pin "3") (pinfunction "3_3") (pintype "passive"))
      (node (ref "Q2") (pin "3") (pinfunction "3_3") (pintype "passive"))
      (node (ref "Q20") (pin "3") (pinfunction "3_3") (pintype "passive"))
      (node (ref "Q21") (pin "3") (pinfunction "3_3") (pintype "passive"))
      (node (ref "Q29") (pin "3") (pinfunction "3_3") (pintype "passive"))
      (node (ref "Q3") (pin "3") (pinfunction "3_3") (pintype "passive"))
      (node (ref "Q30") (pin "3") (pinfunction "3_3") (pintype "passive"))
      (node (ref "Q31") (pin "3") (pinfunction "3_3") (pintype "passive"))
      (node (ref "Q32") (pin "3") (pinfunction "3_3") (pintype "passive"))
      (node (ref "Q33") (pin "3") (pinfunction "3_3") (pintype "passive"))
      (node (ref "Q34") (pin "3") (pinfunction "3_3") (pintype "passive"))
      (node (ref "Q35") (pin "3") (pinfunction "3_3") (pintype "passive"))
      (node (ref "Q4") (pin "3") (pinfunction "3_3") (pintype "passive"))
      (node (ref "Q5") (pin "3") (pinfunction "3_3") (pintype "passive"))
      (node (ref "Q6") (pin "3") (pinfunction "3_3") (pintype "passive"))
      (node (ref "Q7") (pin "3") (pinfunction "3_3") (pintype "passive"))
      (node (ref "R114") (pin "2") (pinfunction "2_2") (pintype "passive"))
      (node (ref "R118") (pin "2") (pinfunction "2_2") (pintype "passive"))
      (node (ref "R122") (pin "2") (pinfunction "2_2") (pintype "passive"))
      (node (ref "T10") (pin "1") (pinfunction "1_1") (pintype "passive"))
      (node (ref "T11") (pin "1") (pinfunction "1_1") (pintype "passive"))
      (node (ref "T12") (pin "1") (pinfunction "1_1") (pintype "passive"))
      (node (ref "T16") (pin "1") (pinfunction "1_1") (pintype "passive"))
      (node (ref "T17") (pin "1") (pinfunction "1_1") (pintype "passive"))
      (node (ref "T18") (pin "1") (pinfunction "1_1") (pintype "passive"))
      (node (ref "T19") (pin "1") (pinfunction "1_1") (pintype "passive"))
      (node (ref "T20") (pin "1") (pinfunction "1_1") (pintype "passive"))
      (node (ref "T21") (pin "1") (pinfunction "1_1") (pintype "passive"))
    )
    (net (code "2") (name "/H1") (class "Default")
      (node (ref "D1") (pin "2") (pinfunction "K_2") (pintype "passive"))
      (node (ref "D2") (pin "2") (pinfunction "K_2") (pintype "passive"))
      (node (ref "D3") (pin "2") (pinfunction "K_2") (pintype "passive"))
      (node (ref "D4") (pin "2") (pinfunction "K_2") (pintype "passive"))
      (node (ref "D5") (pin "2") (pinfunction "K_2") (pintype "passive"))
      (node (ref "D6") (pin "2") (pinfunction "K_2") (pintype "passive"))
      (node (ref "D7") (pin "2") (pinfunction "K_2") (pintype "passive"))
      (node (ref "R1") (pin "1") (pinfunction "1_1") (pintype "passive"))
      (node (ref "R10") (pin "1") (pinfunction "1_1") (pintype "passive"))
      (node (ref "R12") (pin "1") (pinfunction "1_1") (pintype "passive"))
      (node (ref "R2") (pin "1") (pinfunction "1_1") (pintype "passive"))
      (node (ref "R4") (pin "1") (pinfunction "1_1") (pintype "passive"))
      (node (ref "R6") (pin "1") (pinfunction "1_1") (pintype "passive"))
      (node (ref "R8") (pin "1") (pinfunction "1_1") (pintype "passive"))
    )
    (net (code "3") (name "/H2") (class "Default")
      (node (ref "D15") (pin "2") (pinfunction "K_2") (pintype "passive"))
      (node (ref "D16") (pin "2") (pinfunction "K_2") (pintype "passive"))
      (node (ref "D17") (pin "2") (pinfunction "K_2") (pintype "passive"))
      (node (ref "D18") (pin "2") (pinfunction "K_2") (pintype "passive"))
      (node (ref "D19") (pin "2") (pinfunction "K_2") (pintype "passive"))
      (node (ref "D20") (pin "2") (pinfunction "K_2") (pintype "passive"))
      (node (ref "D21") (pin "2") (pinfunction "K_2") (pintype "passive"))
      (node (ref "R32") (pin "1") (pinfunction "1_1") (pintype "passive"))
      (node (ref "R33") (pin "1") (pinfunction "1_1") (pintype "passive"))
      (node (ref "R35") (pin "1") (pinfunction "1_1") (pintype "passive"))
      (node (ref "R37") (pin "1") (pinfunction "1_1") (pintype "passive"))
      (node (ref "R39") (pin "1") (pinfunction "1_1") (pintype "passive"))
      (node (ref "R41") (pin "1") (pinfunction "1_1") (pintype "passive"))
      (node (ref "R43") (pin "1") (pinfunction "1_1") (pintype "passive"))
    )
    (net (code "4") (name "/H3") (class "Default")
      (node (ref "D29") (pin "2") (pinfunction "K_2") (pintype "passive"))
      (node (ref "D30") (pin "2") (pinfunction "K_2") (pintype "passive"))
      (node (ref "D31") (pin "2") (pinfunction "K_2") (pintype "passive"))
      (node (ref "D32") (pin "2") (pinfunction "K_2") (pintype "passive"))
      (node (ref "D33") (pin "2") (pinfunction "K_2") (pintype "passive"))
      (node (ref "D34") (pin "2") (pinfunction "K_2") (pintype "passive"))
      (node (ref "D35") (pin "2") (pinfunction "K_2") (pintype "passive"))
      (node (ref "R63") (pin "1") (pinfunction "1_1") (pintype "passive"))
      (node (ref "R64") (pin "1") (pinfunction "1_1") (pintype "passive"))
      (node (ref "R66") (pin "1") (pinfunction "1_1") (pintype "passive"))
      (node (ref "R68") (pin "1") (pinfunction "1_1") (pintype "passive"))
      (node (ref "R70") (pin "1") (pinfunction "1_1") (pintype "passive"))
      (node (ref "R72") (pin "1") (pinfunction "1_1") (pintype "passive"))
      (node (ref "R74") (pin "1") (pinfunction "1_1") (pintype "passive"))
    )
    (net (code "5") (name "/L1") (class "Default")
      (node (ref "D10") (pin "2") (pinfunction "K_2") (pintype "passive"))
      (node (ref "D11") (pin "2") (pinfunction "K_2") (pintype "passive"))
      (node (ref "D12") (pin "2") (pinfunction "K_2") (pintype "passive"))
      (node (ref "D13") (pin "2") (pinfunction "K_2") (pintype "passive"))
      (node (ref "D14") (pin "2") (pinfunction "K_2") (pintype "passive"))
      (node (ref "D8") (pin "2") (pinfunction "K_2") (pintype "passive"))
      (node (ref "D9") (pin "2") (pinfunction "K_2") (pintype "passive"))
      (node (ref "R15") (pin "1") (pinfunction "1_1") (pintype "passive"))
      (node (ref "R16") (pin "1") (pinfunction "1_1") (pintype "passive"))
      (node (ref "R17") (pin "1") (pinfunction "1_1") (pintype "passive"))
      (node (ref "R18") (pin "1") (pinfunction "1_1") (pintype "passive"))
      (node (ref "R19") (pin "1") (pinfunction "1_1") (pintype "passive"))
      (node (ref "R20") (pin "1") (pinfunction "1_1") (pintype "passive"))
      (node (ref "R21") (pin "1") (pinfunction "1_1") (pintype "passive"))
    )
    (net (code "6") (name "/L2") (class "Default")
      (node (ref "D22") (pin "2") (pinfunction "K_2") (pintype "passive"))
      (node (ref "D23") (pin "2") (pinfunction "K_2") (pintype "passive"))
      (node (ref "D24") (pin "2") (pinfunction "K_2") (pintype "passive"))
      (node (ref "D25") (pin "2") (pinfunction "K_2") (pintype "passive"))
      (node (ref "D26") (pin "2") (pinfunction "K_2") (pintype "passive"))
      (node (ref "D27") (pin "2") (pinfunction "K_2") (pintype "passive"))
      (node (ref "D28") (pin "2") (pinfunction "K_2") (pintype "passive"))
      (node (ref "R46") (pin "1") (pinfunction "1_1") (pintype "passive"))
      (node (ref "R47") (pin "1") (pinfunction "1_1") (pintype "passive"))
      (node (ref "R48") (pin "1") (pinfunction "1_1") (pintype "passive"))
      (node (ref "R49") (pin "1") (pinfunction "1_1") (pintype "passive"))
      (node (ref "R50") (pin "1") (pinfunction "1_1") (pintype "passive"))
      (node (ref "R51") (pin "1") (pinfunction "1_1") (pintype "passive"))
      (node (ref "R52") (pin "1") (pinfunction "1_1") (pintype "passive"))
    )
    (net (code "7") (name "/L3") (class "Default")
      (node (ref "D36") (pin "2") (pinfunction "K_2") (pintype "passive"))
      (node (ref "D37") (pin "2") (pinfunction "K_2") (pintype "passive"))
      (node (ref "D38") (pin "2") (pinfunction "K_2") (pintype "passive"))
      (node (ref "D39") (pin "2") (pinfunction "K_2") (pintype "passive"))
      (node (ref "D40") (pin "2") (pinfunction "K_2") (pintype "passive"))
      (node (ref "D41") (pin "2") (pinfunction "K_2") (pintype "passive"))
      (node (ref "D42") (pin "2") (pinfunction "K_2") (pintype "passive"))
      (node (ref "R77") (pin "1") (pinfunction "1_1") (pintype "passive"))
      (node (ref "R78") (pin "1") (pinfunction "1_1") (pintype "passive"))
      (node (ref "R79") (pin "1") (pinfunction "1_1") (pintype "passive"))
      (node (ref "R80") (pin "1") (pinfunction "1_1") (pintype "passive"))
      (node (ref "R81") (pin "1") (pinfunction "1_1") (pintype "passive"))
      (node (ref "R82") (pin "1") (pinfunction "1_1") (pintype "passive"))
      (node (ref "R83") (pin "1") (pinfunction "1_1") (pintype "passive"))
    )
    (net (code "8") (name "A") (class "Default")
      (node (ref "C72") (pin "1") (pinfunction "1_1") (pintype "passive"))
      (node (ref "C73") (pin "1") (pinfunction "1_1") (pintype "passive"))
      (node (ref "C74") (pin "1") (pinfunction "1_1") (pintype "passive"))
      (node (ref "C93") (pin "1") (pinfunction "1_1") (pintype "passive"))
      (node (ref "C94") (pin "1") (pinfunction "1_1") (pintype "passive"))
      (node (ref "C95") (pin "1") (pinfunction "1_1") (pintype "passive"))
      (node (ref "C96") (pin "1") (pinfunction "1_1") (pintype "passive"))
      (node (ref "Q1") (pin "2") (pinfunction "2_2") (pintype "passive"))
      (node (ref "Q2") (pin "2") (pinfunction "2_2") (pintype "passive"))
      (node (ref "Q3") (pin "2") (pinfunction "2_2") (pintype "passive"))
      (node (ref "Q4") (pin "2") (pinfunction "2_2") (pintype "passive"))
      (node (ref "Q5") (pin "2") (pinfunction "2_2") (pintype "passive"))
      (node (ref "Q6") (pin "2") (pinfunction "2_2") (pintype "passive"))
      (node (ref "Q7") (pin "2") (pinfunction "2_2") (pintype "passive"))
    )
    (net (code "9") (name "A1") (class "Default")
      (node (ref "Q10") (pin "3") (pinfunction "3_3") (pintype "passive"))
      (node (ref "Q11") (pin "3") (pinfunction "3_3") (pintype "passive"))
      (node (ref "Q12") (pin "3") (pinfunction "3_3") (pintype "passive"))
      (node (ref "Q13") (pin "3") (pinfunction "3_3") (pintype "passive"))
      (node (ref "Q14") (pin "3") (pinfunction "3_3") (pintype "passive"))
      (node (ref "Q8") (pin "3") (pinfunction "3_3") (pintype "passive"))
      (node (ref "Q9") (pin "3") (pinfunction "3_3") (pintype "passive"))
      (node (ref "T1") (pin "1") (pinfunction "1_1") (pintype "passive"))
      (node (ref "T2") (pin "1") (pinfunction "1_1") (pintype "passive"))
      (node (ref "T3") (pin "1") (pinfunction "1_1") (pintype "passive"))
    )
    (net (code "10") (name "B") (class "Default")
      (node (ref "C104") (pin "1") (pinfunction "1_1") (pintype "passive"))
      (node (ref "C105") (pin "1") (pinfunction "1_1") (pintype "passive"))
      (node (ref "C106") (pin "1") (pinfunction "1_1") (pintype "passive"))
      (node (ref "C107") (pin "1") (pinfunction "1_1") (pintype "passive"))
      (node (ref "C108") (pin "1") (pinfunction "1_1") (pintype "passive"))
      (node (ref "C109") (pin "1") (pinfunction "1_1") (pintype "passive"))
      (node (ref "C110") (pin "1") (pinfunction "1_1") (pintype "passive"))
      (node (ref "Q15") (pin "2") (pinfunction "2_2") (pintype "passive"))
      (node (ref "Q16") (pin "2") (pinfunction "2_2") (pintype "passive"))
      (node (ref "Q17") (pin "2") (pinfunction "2_2") (pintype "passive"))
      (node (ref "Q18") (pin "2") (pinfunction "2_2") (pintype "passive"))
      (node (ref "Q19") (pin "2") (pinfunction "2_2") (pintype "passive"))
      (node (ref "Q20") (pin "2") (pinfunction "2_2") (pintype "passive"))
      (node (ref "Q21") (pin "2") (pinfunction "2_2") (pintype "passive"))
    )
    (net (code "11") (name "B1") (class "Default")
      (node (ref "Q22") (pin "3") (pinfunction "3_3") (pintype "passive"))
      (node (ref "Q23") (pin "3") (pinfunction "3_3") (pintype "passive"))
      (node (ref "Q24") (pin "3") (pinfunction "3_3") (pintype "passive"))
      (node (ref "Q25") (pin "3") (pinfunction "3_3") (pintype "passive"))
      (node (ref "Q26") (pin "3") (pinfunction "3_3") (pintype "passive"))
      (node (ref "Q27") (pin "3") (pinfunction "3_3") (pintype "passive"))
      (node (ref "Q28") (pin "3") (pinfunction "3_3") (pintype "passive"))
      (node (ref "T4") (pin "1") (pinfunction "1_1") (pintype "passive"))
      (node (ref "T5") (pin "1") (pinfunction "1_1") (pintype "passive"))
      (node (ref "T6") (pin "1") (pinfunction "1_1") (pintype "passive"))
    )
    (net (code "12") (name "GND") (class "Default")
      (node (ref "C100") (pin "1") (pinfunction "1_1") (pintype "passive"))
      (node (ref "C101") (pin "1") (pinfunction "1_1") (pintype "passive"))
      (node (ref "C102") (pin "1") (pinfunction "1_1") (pintype "passive"))
      (node (ref "C103") (pin "1") (pinfunction "1_1") (pintype "passive"))
      (node (ref "C111") (pin "1") (pinfunction "1_1") (pintype "passive"))
      (node (ref "C112") (pin "1") (pinfunction "1_1") (pintype "passive"))
      (node (ref "C113") (pin "1") (pinfunction "1_1") (pintype "passive"))
      (node (ref "C114") (pin "1") (pinfunction "1_1") (pintype "passive"))
      (node (ref "C115") (pin "1") (pinfunction "1_1") (pintype "passive"))
      (node (ref "C116") (pin "1") (pinfunction "1_1") (pintype "passive"))
      (node (ref "C117") (pin "1") (pinfunction "1_1") (pintype "passive"))
      (node (ref "C125") (pin "1") (pinfunction "1_1") (pintype "passive"))
      (node (ref "C126") (pin "1") (pinfunction "1_1") (pintype "passive"))
      (node (ref "C127") (pin "1") (pinfunction "1_1") (pintype "passive"))
      (node (ref "C128") (pin "1") (pinfunction "1_1") (pintype "passive"))
      (node (ref "C129") (pin "1") (pinfunction "1_1") (pintype "passive"))
      (node (ref "C130") (pin "1") (pinfunction "1_1") (pintype "passive"))
      (node (ref "C131") (pin "1") (pinfunction "1_1") (pintype "passive"))
      (node (ref "C97") (pin "1") (pinfunction "1_1") (pintype "passive"))
      (node (ref "C98") (pin "1") (pinfunction "1_1") (pintype "passive"))
      (node (ref "C99") (pin "1") (pinfunction "1_1") (pintype "passive"))
      (node (ref "Q10") (pin "2") (pinfunction "2_2") (pintype "passive"))
      (node (ref "Q11") (pin "2") (pinfunction "2_2") (pintype "passive"))
      (node (ref "Q12") (pin "2") (pinfunction "2_2") (pintype "passive"))
      (node (ref "Q13") (pin "2") (pinfunction "2_2") (pintype "passive"))
      (node (ref "Q14") (pin "2") (pinfunction "2_2") (pintype "passive"))
      (node (ref "Q22") (pin "2") (pinfunction "2_2") (pintype "passive"))
      (node (ref "Q23") (pin "2") (pinfunction "2_2") (pintype "passive"))
      (node (ref "Q24") (pin "2") (pinfunction "2_2") (pintype "passive"))
      (node (ref "Q25") (pin "2") (pinfunction "2_2") (pintype "passive"))
      (node (ref "Q26") (pin "2") (pinfunction "2_2") (pintype "passive"))
      (node (ref "Q27") (pin "2") (pinfunction "2_2") (pintype "passive"))
      (node (ref "Q28") (pin "2") (pinfunction "2_2") (pintype "passive"))
      (node (ref "Q36") (pin "2") (pinfunction "2_2") (pintype "passive"))
      (node (ref "Q37") (pin "2") (pinfunction "2_2") (pintype "passive"))
      (node (ref "Q38") (pin "2") (pinfunction "2_2") (pintype "passive"))
      (node (ref "Q39") (pin "2") (pinfunction "2_2") (pintype "passive"))
      (node (ref "Q40") (pin "2") (pinfunction "2_2") (pintype "passive"))
      (node (ref "Q41") (pin "2") (pinfunction "2_2") (pintype "passive"))
      (node (ref "Q42") (pin "2") (pinfunction "2_2") (pintype "passive"))
      (node (ref "Q8") (pin "2") (pinfunction "2_2") (pintype "passive"))
      (node (ref "Q9") (pin "2") (pinfunction "2_2") (pintype "passive"))
      (node (ref "R117") (pin "1") (pinfunction "1_1") (pintype "passive"))
      (node (ref "R121") (pin "1") (pinfunction "1_1") (pintype "passive"))
      (node (ref "R125") (pin "1") (pinfunction "1_1") (pintype "passive"))
      (node (ref "R30") (pin "1") (pinfunction "1_1") (pintype "passive"))
      (node (ref "R31") (pin "1") (pinfunction "1_1") (pintype "passive"))
      (node (ref "R61") (pin "1") (pinfunction "1_1") (pintype "passive"))
      (node (ref "R62") (pin "1") (pinfunction "1_1") (pintype "passive"))
      (node (ref "R92") (pin "1") (pinfunction "1_1") (pintype "passive"))
      (node (ref "R93") (pin "1") (pinfunction "1_1") (pintype "passive"))
      (node (ref "T13") (pin "1") (pinfunction "1_1") (pintype "passive"))
      (node (ref "T14") (pin "1") (pinfunction "1_1") (pintype "passive"))
      (node (ref "T15") (pin "1") (pinfunction "1_1") (pintype "passive"))
    )
    (net (code "13") (name "Net-(C1-Pad1)") (class "Default")
      (node (ref "C1") (pin "1") (pinfunction "1_1") (pintype "passive"))
      (node (ref "C3") (pin "2") (pinfunction "2_2") (pintype "passive"))
    )
    (net (code "14") (name "Net-(C2-Pad1)") (class "Default")
      (node (ref "C2") (pin "1") (pinfunction "1_1") (pintype "passive"))
      (node (ref "C4") (pin "2") (pinfunction "2_2") (pintype "passive"))
    )
    (net (code "15") (name "Net-(C3-Pad1)") (class "Default")
      (node (ref "C3") (pin "1") (pinfunction "1_1") (pintype "passive"))
      (node (ref "C6") (pin "2") (pinfunction "2_2") (pintype "passive"))
    )
    (net (code "16") (name "Net-(C4-Pad1)") (class "Default")
      (node (ref "C4") (pin "1") (pinfunction "1_1") (pintype "passive"))
      (node (ref "C7") (pin "2") (pinfunction "2_2") (pintype "passive"))
    )
    (net (code "17") (name "Net-(C10-Pad1)") (class "Default")
      (node (ref "C10") (pin "1") (pinfunction "1_1") (pintype "passive"))
      (node (ref "C12") (pin "2") (pinfunction "2_2") (pintype "passive"))
    )
    (net (code "18") (name "Net-(C10-Pad2)") (class "Default")
      (node (ref "C10") (pin "2") (pinfunction "2_2") (pintype "passive"))
      (node (ref "C6") (pin "1") (pinfunction "1_1") (pintype "passive"))
    )
    (net (code "19") (name "Net-(C11-Pad1)") (class "Default")
      (node (ref "C11") (pin "1") (pinfunction "1_1") (pintype "passive"))
      (node (ref "C13") (pin "2") (pinfunction "2_2") (pintype "passive"))
    )
    (net (code "20") (name "Net-(C11-Pad2)") (class "Default")
      (node (ref "C11") (pin "2") (pinfunction "2_2") (pintype "passive"))
      (node (ref "C7") (pin "1") (pinfunction "1_1") (pintype "passive"))
    )
    (net (code "21") (name "Net-(C12-Pad1)") (class "Default")
      (node (ref "C12") (pin "1") (pinfunction "1_1") (pintype "passive"))
      (node (ref "C16") (pin "2") (pinfunction "2_2") (pintype "passive"))
    )
    (net (code "22") (name "Net-(C13-Pad1)") (class "Default")
      (node (ref "C13") (pin "1") (pinfunction "1_1") (pintype "passive"))
      (node (ref "C17") (pin "2") (pinfunction "2_2") (pintype "passive"))
    )
    (net (code "23") (name "Net-(C16-Pad1)") (class "Default")
      (node (ref "C16") (pin "1") (pinfunction "1_1") (pintype "passive"))
      (node (ref "C75") (pin "2") (pinfunction "2_2") (pintype "passive"))
    )
    (net (code "24") (name "Net-(C17-Pad1)") (class "Default")
      (node (ref "C17") (pin "1") (pinfunction "1_1") (pintype "passive"))
      (node (ref "C76") (pin "2") (pinfunction "2_2") (pintype "passive"))
    )
    (net (code "25") (name "Net-(C18-Pad1)") (class "Default")
      (node (ref "C18") (pin "1") (pinfunction "1_1") (pintype "passive"))
      (node (ref "C20") (pin "2") (pinfunction "2_2") (pintype "passive"))
    )
    (net (code "26") (name "Net-(C19-Pad1)") (class "Default")
      (node (ref "C19") (pin "1") (pinfunction "1_1") (pintype "passive"))
      (node (ref "C21") (pin "2") (pinfunction "2_2") (pintype "passive"))
    )
    (net (code "27") (name "Net-(C20-Pad1)") (class "Default")
      (node (ref "C20") (pin "1") (pinfunction "1_1") (pintype "passive"))
      (node (ref "C24") (pin "2") (pinfunction "2_2") (pintype "passive"))
    )
    (net (code "28") (name "Net-(C21-Pad1)") (class "Default")
      (node (ref "C21") (pin "1") (pinfunction "1_1") (pintype "passive"))
      (node (ref "C25") (pin "2") (pinfunction "2_2") (pintype "passive"))
    )
    (net (code "29") (name "Net-(C24-Pad1)") (class "Default")
      (node (ref "C24") (pin "1") (pinfunction "1_1") (pintype "passive"))
      (node (ref "C27") (pin "2") (pinfunction "2_2") (pintype "passive"))
    )
    (net (code "30") (name "Net-(C25-Pad1)") (class "Default")
      (node (ref "C25") (pin "1") (pinfunction "1_1") (pintype "passive"))
      (node (ref "C28") (pin "2") (pinfunction "2_2") (pintype "passive"))
    )
    (net (code "31") (name "Net-(C27-Pad1)") (class "Default")
      (node (ref "C27") (pin "1") (pinfunction "1_1") (pintype "passive"))
      (node (ref "C29") (pin "2") (pinfunction "2_2") (pintype "passive"))
    )
    (net (code "32") (name "Net-(C28-Pad1)") (class "Default")
      (node (ref "C28") (pin "1") (pinfunction "1_1") (pintype "passive"))
      (node (ref "C30") (pin "2") (pinfunction "2_2") (pintype "passive"))
    )
    (net (code "33") (name "Net-(C29-Pad1)") (class "Default")
      (node (ref "C29") (pin "1") (pinfunction "1_1") (pintype "passive"))
      (node (ref "C33") (pin "2") (pinfunction "2_2") (pintype "passive"))
    )
    (net (code "34") (name "Net-(C30-Pad1)") (class "Default")
      (node (ref "C30") (pin "1") (pinfunction "1_1") (pintype "passive"))
      (node (ref "C34") (pin "2") (pinfunction "2_2") (pintype "passive"))
    )
    (net (code "35") (name "Net-(C33-Pad1)") (class "Default")
      (node (ref "C33") (pin "1") (pinfunction "1_1") (pintype "passive"))
      (node (ref "C79") (pin "2") (pinfunction "2_2") (pintype "passive"))
    )
    (net (code "36") (name "Net-(C34-Pad1)") (class "Default")
      (node (ref "C34") (pin "1") (pinfunction "1_1") (pintype "passive"))
      (node (ref "C80") (pin "2") (pinfunction "2_2") (pintype "passive"))
    )
    (net (code "37") (name "Net-(C35-Pad1)") (class "Default")
      (node (ref "C35") (pin "1") (pinfunction "1_1") (pintype "passive"))
      (node (ref "C37") (pin "2") (pinfunction "2_2") (pintype "passive"))
    )
    (net (code "38") (name "Net-(C36-Pad1)") (class "Default")
      (node (ref "C36") (pin "1") (pinfunction "1_1") (pintype "passive"))
      (node (ref "C38") (pin "2") (pinfunction "2_2") (pintype "passive"))
    )
    (net (code "39") (name "Net-(C37-Pad1)") (class "Default")
      (node (ref "C37") (pin "1") (pinfunction "1_1") (pintype "passive"))
      (node (ref "C42") (pin "2") (pinfunction "2_2") (pintype "passive"))
    )
    (net (code "40") (name "Net-(C38-Pad1)") (class "Default")
      (node (ref "C38") (pin "1") (pinfunction "1_1") (pintype "passive"))
      (node (ref "C43") (pin "2") (pinfunction "2_2") (pintype "passive"))
    )
    (net (code "41") (name "Net-(C42-Pad1)") (class "Default")
      (node (ref "C42") (pin "1") (pinfunction "1_1") (pintype "passive"))
      (node (ref "C44") (pin "2") (pinfunction "2_2") (pintype "passive"))
    )
    (net (code "42") (name "Net-(C43-Pad1)") (class "Default")
      (node (ref "C43") (pin "1") (pinfunction "1_1") (pintype "passive"))
      (node (ref "C45") (pin "2") (pinfunction "2_2") (pintype "passive"))
    )
    (net (code "43") (name "Net-(C44-Pad1)") (class "Default")
      (node (ref "C44") (pin "1") (pinfunction "1_1") (pintype "passive"))
      (node (ref "C46") (pin "2") (pinfunction "2_2") (pintype "passive"))
    )
    (net (code "44") (name "Net-(C45-Pad1)") (class "Default")
      (node (ref "C45") (pin "1") (pinfunction "1_1") (pintype "passive"))
      (node (ref "C47") (pin "2") (pinfunction "2_2") (pintype "passive"))
    )
    (net (code "45") (name "Net-(C46-Pad1)") (class "Default")
      (node (ref "C46") (pin "1") (pinfunction "1_1") (pintype "passive"))
      (node (ref "C50") (pin "2") (pinfunction "2_2") (pintype "passive"))
    )
    (net (code "46") (name "Net-(C47-Pad1)") (class "Default")
      (node (ref "C47") (pin "1") (pinfunction "1_1") (pintype "passive"))
      (node (ref "C51") (pin "2") (pinfunction "2_2") (pintype "passive"))
    )
    (net (code "47") (name "Net-(C50-Pad1)") (class "Default")
      (node (ref "C50") (pin "1") (pinfunction "1_1") (pintype "passive"))
      (node (ref "C83") (pin "2") (pinfunction "2_2") (pintype "passive"))
    )
    (net (code "48") (name "Net-(C51-Pad1)") (class "Default")
      (node (ref "C51") (pin "1") (pinfunction "1_1") (pintype "passive"))
      (node (ref "C84") (pin "2") (pinfunction "2_2") (pintype "passive"))
    )
    (net (code "49") (name "Net-(C72-Pad2)") (class "Default")
      (node (ref "C72") (pin "2") (pinfunction "2_2") (pintype "passive"))
      (node (ref "R14") (pin "1") (pinfunction "1_1") (pintype "passive"))
    )
    (net (code "50") (name "Net-(C73-Pad2)") (class "Default")
      (node (ref "C73") (pin "2") (pinfunction "2_2") (pintype "passive"))
      (node (ref "R3") (pin "1") (pinfunction "1_1") (pintype "passive"))
    )
    (net (code "51") (name "Net-(C74-Pad2)") (class "Default")
      (node (ref "C74") (pin "2") (pinfunction "2_2") (pintype "passive"))
      (node (ref "R5") (pin "1") (pinfunction "1_1") (pintype "passive"))
    )
    (net (code "52") (name "Net-(C75-Pad1)") (class "Default")
      (node (ref "C75") (pin "1") (pinfunction "1_1") (pintype "passive"))
      (node (ref "C77") (pin "2") (pinfunction "2_2") (pintype "passive"))
    )
    (net (code "53") (name "Net-(C76-Pad1)") (class "Default")
      (node (ref "C76") (pin "1") (pinfunction "1_1") (pintype "passive"))
      (node (ref "C78") (pin "2") (pinfunction "2_2") (pintype "passive"))
    )
    (net (code "54") (name "Net-(C77-Pad1)") (class "Default")
      (node (ref "C77") (pin "1") (pinfunction "1_1") (pintype "passive"))
      (node (ref "R30") (pin "2") (pinfunction "2_2") (pintype "passive"))
    )
    (net (code "55") (name "Net-(C78-Pad1)") (class "Default")
      (node (ref "C78") (pin "1") (pinfunction "1_1") (pintype "passive"))
      (node (ref "R31") (pin "2") (pinfunction "2_2") (pintype "passive"))
    )
    (net (code "56") (name "Net-(C79-Pad1)") (class "Default")
      (node (ref "C79") (pin "1") (pinfunction "1_1") (pintype "passive"))
      (node (ref "C81") (pin "2") (pinfunction "2_2") (pintype "passive"))
    )
    (net (code "57") (name "Net-(C80-Pad1)") (class "Default")
      (node (ref "C80") (pin "1") (pinfunction "1_1") (pintype "passive"))
      (node (ref "C82") (pin "2") (pinfunction "2_2") (pintype "passive"))
    )
    (net (code "58") (name "Net-(C81-Pad1)") (class "Default")
      (node (ref "C81") (pin "1") (pinfunction "1_1") (pintype "passive"))
      (node (ref "R61") (pin "2") (pinfunction "2_2") (pintype "passive"))
    )
    (net (code "59") (name "Net-(C82-Pad1)") (class "Default")
      (node (ref "C82") (pin "1") (pinfunction "1_1") (pintype "passive"))
      (node (ref "R62") (pin "2") (pinfunction "2_2") (pintype "passive"))
    )
    (net (code "60") (name "Net-(C83-Pad1)") (class "Default")
      (node (ref "C83") (pin "1") (pinfunction "1_1") (pintype "passive"))
      (node (ref "C85") (pin "2") (pinfunction "2_2") (pintype "passive"))
    )
    (net (code "61") (name "Net-(C84-Pad1)") (class "Default")
      (node (ref "C84") (pin "1") (pinfunction "1_1") (pintype "passive"))
      (node (ref "C86") (pin "2") (pinfunction "2_2") (pintype "passive"))
    )
    (net (code "62") (name "Net-(C85-Pad1)") (class "Default")
      (node (ref "C85") (pin "1") (pinfunction "1_1") (pintype "passive"))
      (node (ref "R92") (pin "2") (pinfunction "2_2") (pintype "passive"))
    )
    (net (code "63") (name "Net-(C86-Pad1)") (class "Default")
      (node (ref "C86") (pin "1") (pinfunction "1_1") (pintype "passive"))
      (node (ref "R93") (pin "2") (pinfunction "2_2") (pintype "passive"))
    )
    (net (code "64") (name "Net-(C93-Pad2)") (class "Default")
      (node (ref "C93") (pin "2") (pinfunction "2_2") (pintype "passive"))
      (node (ref "R7") (pin "1") (pinfunction "1_1") (pintype "passive"))
    )
    (net (code "65") (name "Net-(C94-Pad2)") (class "Default")
      (node (ref "C94") (pin "2") (pinfunction "2_2") (pintype "passive"))
      (node (ref "R9") (pin "1") (pinfunction "1_1") (pintype "passive"))
    )
    (net (code "66") (name "Net-(C95-Pad2)") (class "Default")
      (node (ref "C95") (pin "2") (pinfunction "2_2") (pintype "passive"))
      (node (ref "R11") (pin "1") (pinfunction "1_1") (pintype "passive"))
    )
    (net (code "67") (name "Net-(C96-Pad2)") (class "Default")
      (node (ref "C96") (pin "2") (pinfunction "2_2") (pintype "passive"))
      (node (ref "R13") (pin "1") (pinfunction "1_1") (pintype "passive"))
    )
    (net (code "68") (name "Net-(C97-Pad2)") (class "Default")
      (node (ref "C97") (pin "2") (pinfunction "2_2") (pintype "passive"))
      (node (ref "R23") (pin "1") (pinfunction "1_1") (pintype "passive"))
    )
    (net (code "69") (name "Net-(C98-Pad2)") (class "Default")
      (node (ref "C98") (pin "2") (pinfunction "2_2") (pintype "passive"))
      (node (ref "R24") (pin "1") (pinfunction "1_1") (pintype "passive"))
    )
    (net (code "70") (name "Net-(C99-Pad2)") (class "Default")
      (node (ref "C99") (pin "2") (pinfunction "2_2") (pintype "passive"))
      (node (ref "R25") (pin "1") (pinfunction "1_1") (pintype "passive"))
    )
    (net (code "71") (name "Net-(C100-Pad2)") (class "Default")
      (node (ref "C100") (pin "2") (pinfunction "2_2") (pintype "passive"))
      (node (ref "R26") (pin "1") (pinfunction "1_1") (pintype "passive"))
    )
    (net (code "72") (name "Net-(C101-Pad2)") (class "Default")
      (node (ref "C101") (pin "2") (pinfunction "2_2") (pintype "passive"))
      (node (ref "R27") (pin "1") (pinfunction "1_1") (pintype "passive"))
    )
    (net (code "73") (name "Net-(C102-Pad2)") (class "Default")
      (node (ref "C102") (pin "2") (pinfunction "2_2") (pintype "passive"))
      (node (ref "R28") (pin "1") (pinfunction "1_1") (pintype "passive"))
    )
    (net (code "74") (name "Net-(C103-Pad2)") (class "Default")
      (node (ref "C103") (pin "2") (pinfunction "2_2") (pintype "passive"))
      (node (ref "R29") (pin "1") (pinfunction "1_1") (pintype "passive"))
    )
    (net (code "75") (name "Net-(C104-Pad2)") (class "Default")
      (node (ref "C104") (pin "2") (pinfunction "2_2") (pintype "passive"))
      (node (ref "R34") (pin "1") (pinfunction "1_1") (pintype "passive"))
    )
    (net (code "76") (name "Net-(C105-Pad2)") (class "Default")
      (node (ref "C105") (pin "2") (pinfunction "2_2") (pintype "passive"))
      (node (ref "R36") (pin "1") (pinfunction "1_1") (pintype "passive"))
    )
    (net (code "77") (name "Net-(C106-Pad2)") (class "Default")
      (node (ref "C106") (pin "2") (pinfunction "2_2") (pintype "passive"))
      (node (ref "R38") (pin "1") (pinfunction "1_1") (pintype "passive"))
    )
    (net (code "78") (name "Net-(C107-Pad2)") (class "Default")
      (node (ref "C107") (pin "2") (pinfunction "2_2") (pintype "passive"))
      (node (ref "R40") (pin "1") (pinfunction "1_1") (pintype "passive"))
    )
    (net (code "79") (name "Net-(C108-Pad2)") (class "Default")
      (node (ref "C108") (pin "2") (pinfunction "2_2") (pintype "passive"))
      (node (ref "R42") (pin "1") (pinfunction "1_1") (pintype "passive"))
    )
    (net (code "80") (name "Net-(C109-Pad2)") (class "Default")
      (node (ref "C109") (pin "2") (pinfunction "2_2") (pintype "passive"))
      (node (ref "R44") (pin "1") (pinfunction "1_1") (pintype "passive"))
    )
    (net (code "81") (name "Net-(C110-Pad2)") (class "Default")
      (node (ref "C110") (pin "2") (pinfunction "2_2") (pintype "passive"))
      (node (ref "R45") (pin "1") (pinfunction "1_1") (pintype "passive"))
    )
    (net (code "82") (name "Net-(C111-Pad2)") (class "Default")
      (node (ref "C111") (pin "2") (pinfunction "2_2") (pintype "passive"))
      (node (ref "R54") (pin "1") (pinfunction "1_1") (pintype "passive"))
    )
    (net (code "83") (name "Net-(C112-Pad2)") (class "Default")
      (node (ref "C112") (pin "2") (pinfunction "2_2") (pintype "passive"))
      (node (ref "R55") (pin "1") (pinfunction "1_1") (pintype "passive"))
    )
    (net (code "84") (name "Net-(C113-Pad2)") (class "Default")
      (node (ref "C113") (pin "2") (pinfunction "2_2") (pintype "passive"))
      (node (ref "R56") (pin "1") (pinfunction "1_1") (pintype "passive"))
    )
    (net (code "85") (name "Net-(C114-Pad2)") (class "Default")
      (node (ref "C114") (pin "2") (pinfunction "2_2") (pintype "passive"))
      (node (ref "R57") (pin "1") (pinfunction "1_1") (pintype "passive"))
    )
    (net (code "86") (name "Net-(C115-Pad2)") (class "Default")
      (node (ref "C115") (pin "2") (pinfunction "2_2") (pintype "passive"))
      (node (ref "R58") (pin "1") (pinfunction "1_1") (pintype "passive"))
    )
    (net (code "87") (name "Net-(C116-Pad2)") (class "Default")
      (node (ref "C116") (pin "2") (pinfunction "2_2") (pintype "passive"))
      (node (ref "R59") (pin "1") (pinfunction "1_1") (pintype "passive"))
    )
    (net (code "88") (name "Net-(C117-Pad2)") (class "Default")
      (node (ref "C117") (pin "2") (pinfunction "2_2") (pintype "passive"))
      (node (ref "R60") (pin "1") (pinfunction "1_1") (pintype "passive"))
    )
    (net (code "89") (name "Net-(C118-Pad2)") (class "Default")
      (node (ref "C118") (pin "2") (pinfunction "2_2") (pintype "passive"))
      (node (ref "R65") (pin "1") (pinfunction "1_1") (pintype "passive"))
    )
    (net (code "90") (name "Net-(C119-Pad2)") (class "Default")
      (node (ref "C119") (pin "2") (pinfunction "2_2") (pintype "passive"))
      (node (ref "R67") (pin "1") (pinfunction "1_1") (pintype "passive"))
    )
    (net (code "91") (name "Net-(C120-Pad2)") (class "Default")
      (node (ref "C120") (pin "2") (pinfunction "2_2") (pintype "passive"))
      (node (ref "R69") (pin "1") (pinfunction "1_1") (pintype "passive"))
    )
    (net (code "92") (name "Net-(C121-Pad2)") (class "Default")
      (node (ref "C121") (pin "2") (pinfunction "2_2") (pintype "passive"))
      (node (ref "R71") (pin "1") (pinfunction "1_1") (pintype "passive"))
    )
    (net (code "93") (name "Net-(C122-Pad2)") (class "Default")
      (node (ref "C122") (pin "2") (pinfunction "2_2") (pintype "passive"))
      (node (ref "R73") (pin "1") (pinfunction "1_1") (pintype "passive"))
    )
    (net (code "94") (name "Net-(C123-Pad2)") (class "Default")
      (node (ref "C123") (pin "2") (pinfunction "2_2") (pintype "passive"))
      (node (ref "R75") (pin "1") (pinfunction "1_1") (pintype "passive"))
    )
    (net (code "95") (name "Net-(C124-Pad2)") (class "Default")
      (node (ref "C124") (pin "2") (pinfunction "2_2") (pintype "passive"))
      (node (ref "R76") (pin "1") (pinfunction "1_1") (pintype "passive"))
    )
    (net (code "96") (name "Net-(C125-Pad2)") (class "Default")
      (node (ref "C125") (pin "2") (pinfunction "2_2") (pintype "passive"))
      (node (ref "R85") (pin "1") (pinfunction "1_1") (pintype "passive"))
    )
    (net (code "97") (name "Net-(C126-Pad2)") (class "Default")
      (node (ref "C126") (pin "2") (pinfunction "2_2") (pintype "passive"))
      (node (ref "R86") (pin "1") (pinfunction "1_1") (pintype "passive"))
    )
    (net (code "98") (name "Net-(C127-Pad2)") (class "Default")
      (node (ref "C127") (pin "2") (pinfunction "2_2") (pintype "passive"))
      (node (ref "R87") (pin "1") (pinfunction "1_1") (pintype "passive"))
    )
    (net (code "99") (name "Net-(C128-Pad2)") (class "Default")
      (node (ref "C128") (pin "2") (pinfunction "2_2") (pintype "passive"))
      (node (ref "R88") (pin "1") (pinfunction "1_1") (pintype "passive"))
    )
    (net (code "100") (name "Net-(C129-Pad2)") (class "Default")
      (node (ref "C129") (pin "2") (pinfunction "2_2") (pintype "passive"))
      (node (ref "R89") (pin "1") (pinfunction "1_1") (pintype "passive"))
    )
    (net (code "101") (name "Net-(C130-Pad2)") (class "Default")
      (node (ref "C130") (pin "2") (pinfunction "2_2") (pintype "passive"))
      (node (ref "R90") (pin "1") (pinfunction "1_1") (pintype "passive"))
    )
    (net (code "102") (name "Net-(C131-Pad2)") (class "Default")
      (node (ref "C131") (pin "2") (pinfunction "2_2") (pintype "passive"))
      (node (ref "R91") (pin "1") (pinfunction "1_1") (pintype "passive"))
    )
    (net (code "103") (name "Net-(D1-A)") (class "Default")
      (node (ref "D1") (pin "1") (pinfunction "A_1") (pintype "passive"))
      (node (ref "R161") (pin "1") (pinfunction "1_1") (pintype "passive"))
    )
    (net (code "104") (name "Net-(D2-A)") (class "Default")
      (node (ref "D2") (pin "1") (pinfunction "A_1") (pintype "passive"))
      (node (ref "R155") (pin "1") (pinfunction "1_1") (pintype "passive"))
    )
    (net (code "105") (name "Net-(D3-A)") (class "Default")
      (node (ref "D3") (pin "1") (pinfunction "A_1") (pintype "passive"))
      (node (ref "R156") (pin "1") (pinfunction "1_1") (pintype "passive"))
    )
    (net (code "106") (name "Net-(D4-A)") (class "Default")
      (node (ref "D4") (pin "1") (pinfunction "A_1") (pintype "passive"))
      (node (ref "R157") (pin "1") (pinfunction "1_1") (pintype "passive"))
    )
    (net (code "107") (name "Net-(D5-A)") (class "Default")
      (node (ref "D5") (pin "1") (pinfunction "A_1") (pintype "passive"))
      (node (ref "R158") (pin "1") (pinfunction "1_1") (pintype "passive"))
    )
    (net (code "108") (name "Net-(D6-A)") (class "Default")
      (node (ref "D6") (pin "1") (pinfunction "A_1") (pintype "passive"))
      (node (ref "R159") (pin "1") (pinfunction "1_1") (pintype "passive"))
    )
    (net (code "109") (name "Net-(D7-A)") (class "Default")
      (node (ref "D7") (pin "1") (pinfunction "A_1") (pintype "passive"))
      (node (ref "R160") (pin "1") (pinfunction "1_1") (pintype "passive"))
    )
    (net (code "110") (name "Net-(D8-A)") (class "Default")
      (node (ref "D8") (pin "1") (pinfunction "A_1") (pintype "passive"))
      (node (ref "R164") (pin "1") (pinfunction "1_1") (pintype "passive"))
    )
    (net (code "111") (name "Net-(D9-A)") (class "Default")
      (node (ref "D9") (pin "1") (pinfunction "A_1") (pintype "passive"))
      (node (ref "R165") (pin "1") (pinfunction "1_1") (pintype "passive"))
    )
    (net (code "112") (name "Net-(D10-A)") (class "Default")
      (node (ref "D10") (pin "1") (pinfunction "A_1") (pintype "passive"))
      (node (ref "R168") (pin "1") (pinfunction "1_1") (pintype "passive"))
    )
    (net (code "113") (name "Net-(D11-A)") (class "Default")
      (node (ref "D11") (pin "1") (pinfunction "A_1") (pintype "passive"))
      (node (ref "R163") (pin "1") (pinfunction "1_1") (pintype "passive"))
    )
    (net (code "114") (name "Net-(D12-A)") (class "Default")
      (node (ref "D12") (pin "1") (pinfunction "A_1") (pintype "passive"))
      (node (ref "R162") (pin "1") (pinfunction "1_1") (pintype "passive"))
    )
    (net (code "115") (name "Net-(D13-A)") (class "Default")
      (node (ref "D13") (pin "1") (pinfunction "A_1") (pintype "passive"))
      (node (ref "R166") (pin "1") (pinfunction "1_1") (pintype "passive"))
    )
    (net (code "116") (name "Net-(D14-A)") (class "Default")
      (node (ref "D14") (pin "1") (pinfunction "A_1") (pintype "passive"))
      (node (ref "R167") (pin "1") (pinfunction "1_1") (pintype "passive"))
    )
    (net (code "117") (name "Net-(D15-A)") (class "Default")
      (node (ref "D15") (pin "1") (pinfunction "A_1") (pintype "passive"))
      (node (ref "R175") (pin "1") (pinfunction "1_1") (pintype "passive"))
    )
    (net (code "118") (name "Net-(D16-A)") (class "Default")
      (node (ref "D16") (pin "1") (pinfunction "A_1") (pintype "passive"))
      (node (ref "R169") (pin "1") (pinfunction "1_1") (pintype "passive"))
    )
    (net (code "119") (name "Net-(D17-A)") (class "Default")
      (node (ref "D17") (pin "1") (pinfunction "A_1") (pintype "passive"))
      (node (ref "R170") (pin "1") (pinfunction "1_1") (pintype "passive"))
    )
    (net (code "120") (name "Net-(D18-A)") (class "Default")
      (node (ref "D18") (pin "1") (pinfunction "A_1") (pintype "passive"))
      (node (ref "R171") (pin "1") (pinfunction "1_1") (pintype "passive"))
    )
    (net (code "121") (name "Net-(D19-A)") (class "Default")
      (node (ref "D19") (pin "1") (pinfunction "A_1") (pintype "passive"))
      (node (ref "R172") (pin "1") (pinfunction "1_1") (pintype "passive"))
    )
    (net (code "122") (name "Net-(D20-A)") (class "Default")
      (node (ref "D20") (pin "1") (pinfunction "A_1") (pintype "passive"))
      (node (ref "R173") (pin "1") (pinfunction "1_1") (pintype "passive"))
    )
    (net (code "123") (name "Net-(D21-A)") (class "Default")
      (node (ref "D21") (pin "1") (pinfunction "A_1") (pintype "passive"))
      (node (ref "R174") (pin "1") (pinfunction "1_1") (pintype "passive"))
    )
    (net (code "124") (name "Net-(D22-A)") (class "Default")
      (node (ref "D22") (pin "1") (pinfunction "A_1") (pintype "passive"))
      (node (ref "R179") (pin "2") (pinfunction "2_2") (pintype "passive"))
    )
    (net (code "125") (name "Net-(D23-A)") (class "Default")
      (node (ref "D23") (pin "1") (pinfunction "A_1") (pintype "passive"))
      (node (ref "R180") (pin "2") (pinfunction "2_2") (pintype "passive"))
    )
    (net (code "126") (name "Net-(D24-A)") (class "Default")
      (node (ref "D24") (pin "1") (pinfunction "A_1") (pintype "passive"))
      (node (ref "R182") (pin "2") (pinfunction "2_2") (pintype "passive"))
    )
    (net (code "127") (name "Net-(D25-A)") (class "Default")
      (node (ref "D25") (pin "1") (pinfunction "A_1") (pintype "passive"))
      (node (ref "R176") (pin "1") (pinfunction "1_1") (pintype "passive"))
    )
    (net (code "128") (name "Net-(D26-A)") (class "Default")
      (node (ref "D26") (pin "1") (pinfunction "A_1") (pintype "passive"))
      (node (ref "R181") (pin "2") (pinfunction "2_2") (pintype "passive"))
    )
    (net (code "129") (name "Net-(D27-A)") (class "Default")
      (node (ref "D27") (pin "1") (pinfunction "A_1") (pintype "passive"))
      (node (ref "R177") (pin "2") (pinfunction "2_2") (pintype "passive"))
    )
    (net (code "130") (name "Net-(D28-A)") (class "Default")
      (node (ref "D28") (pin "1") (pinfunction "A_1") (pintype "passive"))
      (node (ref "R178") (pin "2") (pinfunction "2_2") (pintype "passive"))
    )
    (net (code "131") (name "Net-(D29-A)") (class "Default")
      (node (ref "D29") (pin "1") (pinfunction "A_1") (pintype "passive"))
      (node (ref "R189") (pin "1") (pinfunction "1_1") (pintype "passive"))
    )
    (net (code "132") (name "Net-(D30-A)") (class "Default")
      (node (ref "D30") (pin "1") (pinfunction "A_1") (pintype "passive"))
      (node (ref "R183") (pin "1") (pinfunction "1_1") (pintype "passive"))
    )
    (net (code "133") (name "Net-(D31-A)") (class "Default")
      (node (ref "D31") (pin "1") (pinfunction "A_1") (pintype "passive"))
      (node (ref "R184") (pin "1") (pinfunction "1_1") (pintype "passive"))
    )
    (net (code "134") (name "Net-(D32-A)") (class "Default")
      (node (ref "D32") (pin "1") (pinfunction "A_1") (pintype "passive"))
      (node (ref "R185") (pin "1") (pinfunction "1_1") (pintype "passive"))
    )
    (net (code "135") (name "Net-(D33-A)") (class "Default")
      (node (ref "D33") (pin "1") (pinfunction "A_1") (pintype "passive"))
      (node (ref "R186") (pin "1") (pinfunction "1_1") (pintype "passive"))
    )
    (net (code "136") (name "Net-(D34-A)") (class "Default")
      (node (ref "D34") (pin "1") (pinfunction "A_1") (pintype "passive"))
      (node (ref "R187") (pin "1") (pinfunction "1_1") (pintype "passive"))
    )
    (net (code "137") (name "Net-(D35-A)") (class "Default")
      (node (ref "D35") (pin "1") (pinfunction "A_1") (pintype "passive"))
      (node (ref "R188") (pin "1") (pinfunction "1_1") (pintype "passive"))
    )
    (net (code "138") (name "Net-(D36-A)") (class "Default")
      (node (ref "D36") (pin "1") (pinfunction "A_1") (pintype "passive"))
      (node (ref "R192") (pin "2") (pinfunction "2_2") (pintype "passive"))
    )
    (net (code "139") (name "Net-(D37-A)") (class "Default")
      (node (ref "D37") (pin "1") (pinfunction "A_1") (pintype "passive"))
      (node (ref "R193") (pin "2") (pinfunction "2_2") (pintype "passive"))
    )
    (net (code "140") (name "Net-(D38-A)") (class "Default")
      (node (ref "D38") (pin "1") (pinfunction "A_1") (pintype "passive"))
      (node (ref "R196") (pin "2") (pinfunction "2_2") (pintype "passive"))
    )
    (net (code "141") (name "Net-(D39-A)") (class "Default")
      (node (ref "D39") (pin "1") (pinfunction "A_1") (pintype "passive"))
      (node (ref "R191") (pin "2") (pinfunction "2_2") (pintype "passive"))
    )
    (net (code "142") (name "Net-(D40-A)") (class "Default")
      (node (ref "D40") (pin "1") (pinfunction "A_1") (pintype "passive"))
      (node (ref "R190") (pin "2") (pinfunction "2_2") (pintype "passive"))
    )
    (net (code "143") (name "Net-(D41-A)") (class "Default")
      (node (ref "D41") (pin "1") (pinfunction "A_1") (pintype "passive"))
      (node (ref "R194") (pin "2") (pinfunction "2_2") (pintype "passive"))
    )
    (net (code "144") (name "Net-(D42-A)") (class "Default")
      (node (ref "D42") (pin "1") (pinfunction "A_1") (pintype "passive"))
      (node (ref "R195") (pin "2") (pinfunction "2_2") (pintype "passive"))
    )
    (net (code "145") (name "Net-(Q1-Pad1)") (class "Default")
      (node (ref "Q1") (pin "1") (pinfunction "1_1") (pintype "passive"))
      (node (ref "R155") (pin "2") (pinfunction "2_2") (pintype "passive"))
      (node (ref "R2") (pin "2") (pinfunction "2_2") (pintype "passive"))
      (node (ref "R3") (pin "2") (pinfunction "2_2") (pintype "passive"))
    )
    (net (code "146") (name "Net-(Q2-Pad1)") (class "Default")
      (node (ref "Q2") (pin "1") (pinfunction "1_1") (pintype "passive"))
      (node (ref "R157") (pin "2") (pinfunction "2_2") (pintype "passive"))
      (node (ref "R6") (pin "2") (pinfunction "2_2") (pintype "passive"))
      (node (ref "R7") (pin "2") (pinfunction "2_2") (pintype "passive"))
    )
    (net (code "147") (name "Net-(Q3-Pad1)") (class "Default")
      (node (ref "Q3") (pin "1") (pinfunction "1_1") (pintype "passive"))
      (node (ref "R158") (pin "2") (pinfunction "2_2") (pintype "passive"))
      (node (ref "R8") (pin "2") (pinfunction "2_2") (pintype "passive"))
      (node (ref "R9") (pin "2") (pinfunction "2_2") (pintype "passive"))
    )
    (net (code "148") (name "Net-(Q4-Pad1)") (class "Default")
      (node (ref "Q4") (pin "1") (pinfunction "1_1") (pintype "passive"))
      (node (ref "R10") (pin "2") (pinfunction "2_2") (pintype "passive"))
      (node (ref "R11") (pin "2") (pinfunction "2_2") (pintype "passive"))
      (node (ref "R159") (pin "2") (pinfunction "2_2") (pintype "passive"))
    )
    (net (code "149") (name "Net-(Q5-Pad1)") (class "Default")
      (node (ref "Q5") (pin "1") (pinfunction "1_1") (pintype "passive"))
      (node (ref "R12") (pin "2") (pinfunction "2_2") (pintype "passive"))
      (node (ref "R13") (pin "2") (pinfunction "2_2") (pintype "passive"))
      (node (ref "R160") (pin "2") (pinfunction "2_2") (pintype "passive"))
    )
    (net (code "150") (name "Net-(Q6-Pad1)") (class "Default")
      (node (ref "Q6") (pin "1") (pinfunction "1_1") (pintype "passive"))
      (node (ref "R156") (pin "2") (pinfunction "2_2") (pintype "passive"))
      (node (ref "R4") (pin "2") (pinfunction "2_2") (pintype "passive"))
      (node (ref "R5") (pin "2") (pinfunction "2_2") (pintype "passive"))
    )
    (net (code "151") (name "Net-(Q7-Pad1)") (class "Default")
      (node (ref "Q7") (pin "1") (pinfunction "1_1") (pintype "passive"))
      (node (ref "R1") (pin "2") (pinfunction "2_2") (pintype "passive"))
      (node (ref "R14") (pin "2") (pinfunction "2_2") (pintype "passive"))
      (node (ref "R161") (pin "2") (pinfunction "2_2") (pintype "passive"))
    )
    (net (code "152") (name "Net-(Q8-Pad1)") (class "Default")
      (node (ref "Q8") (pin "1") (pinfunction "1_1") (pintype "passive"))
      (node (ref "R167") (pin "2") (pinfunction "2_2") (pintype "passive"))
      (node (ref "R21") (pin "2") (pinfunction "2_2") (pintype "passive"))
      (node (ref "R26") (pin "2") (pinfunction "2_2") (pintype "passive"))
    )
    (net (code "153") (name "Net-(Q9-Pad1)") (class "Default")
      (node (ref "Q9") (pin "1") (pinfunction "1_1") (pintype "passive"))
      (node (ref "R164") (pin "2") (pinfunction "2_2") (pintype "passive"))
      (node (ref "R18") (pin "2") (pinfunction "2_2") (pintype "passive"))
      (node (ref "R23") (pin "2") (pinfunction "2_2") (pintype "passive"))
    )
    (net (code "154") (name "Net-(Q10-Pad1)") (class "Default")
      (node (ref "Q10") (pin "1") (pinfunction "1_1") (pintype "passive"))
      (node (ref "R16") (pin "2") (pinfunction "2_2") (pintype "passive"))
      (node (ref "R165") (pin "2") (pinfunction "2_2") (pintype "passive"))
      (node (ref "R24") (pin "2") (pinfunction "2_2") (pintype "passive"))
    )
    (net (code "155") (name "Net-(Q11-Pad1)") (class "Default")
      (node (ref "Q11") (pin "1") (pinfunction "1_1") (pintype "passive"))
      (node (ref "R166") (pin "2") (pinfunction "2_2") (pintype "passive"))
      (node (ref "R20") (pin "2") (pinfunction "2_2") (pintype "passive"))
      (node (ref "R25") (pin "2") (pinfunction "2_2") (pintype "passive"))
    )
    (net (code "156") (name "Net-(Q12-Pad1)") (class "Default")
      (node (ref "Q12") (pin "1") (pinfunction "1_1") (pintype "passive"))
      (node (ref "R162") (pin "2") (pinfunction "2_2") (pintype "passive"))
      (node (ref "R19") (pin "2") (pinfunction "2_2") (pintype "passive"))
      (node (ref "R29") (pin "2") (pinfunction "2_2") (pintype "passive"))
    )
    (net (code "157") (name "Net-(Q13-Pad1)") (class "Default")
      (node (ref "Q13") (pin "1") (pinfunction "1_1") (pintype "passive"))
      (node (ref "R163") (pin "2") (pinfunction "2_2") (pintype "passive"))
      (node (ref "R17") (pin "2") (pinfunction "2_2") (pintype "passive"))
      (node (ref "R28") (pin "2") (pinfunction "2_2") (pintype "passive"))
    )
    (net (code "158") (name "Net-(Q14-Pad1)") (class "Default")
      (node (ref "Q14") (pin "1") (pinfunction "1_1") (pintype "passive"))
      (node (ref "R15") (pin "2") (pinfunction "2_2") (pintype "passive"))
      (node (ref "R168") (pin "2") (pinfunction "2_2") (pintype "passive"))
      (node (ref "R27") (pin "2") (pinfunction "2_2") (pintype "passive"))
    )
    (net (code "159") (name "Net-(Q15-Pad1)") (class "Default")
      (node (ref "Q15") (pin "1") (pinfunction "1_1") (pintype "passive"))
      (node (ref "R171") (pin "2") (pinfunction "2_2") (pintype "passive"))
      (node (ref "R37") (pin "2") (pinfunction "2_2") (pintype "passive"))
      (node (ref "R38") (pin "2") (pinfunction "2_2") (pintype "passive"))
    )
    (net (code "160") (name "Net-(Q16-Pad1)") (class "Default")
      (node (ref "Q16") (pin "1") (pinfunction "1_1") (pintype "passive"))
      (node (ref "R169") (pin "2") (pinfunction "2_2") (pintype "passive"))
      (node (ref "R33") (pin "2") (pinfunction "2_2") (pintype "passive"))
      (node (ref "R34") (pin "2") (pinfunction "2_2") (pintype "passive"))
    )
    (net (code "161") (name "Net-(Q17-Pad1)") (class "Default")
      (node (ref "Q17") (pin "1") (pinfunction "1_1") (pintype "passive"))
      (node (ref "R173") (pin "2") (pinfunction "2_2") (pintype "passive"))
      (node (ref "R41") (pin "2") (pinfunction "2_2") (pintype "passive"))
      (node (ref "R42") (pin "2") (pinfunction "2_2") (pintype "passive"))
    )
    (net (code "162") (name "Net-(Q18-Pad1)") (class "Default")
      (node (ref "Q18") (pin "1") (pinfunction "1_1") (pintype "passive"))
      (node (ref "R170") (pin "2") (pinfunction "2_2") (pintype "passive"))
      (node (ref "R35") (pin "2") (pinfunction "2_2") (pintype "passive"))
      (node (ref "R36") (pin "2") (pinfunction "2_2") (pintype "passive"))
    )
    (net (code "163") (name "Net-(Q19-Pad1)") (class "Default")
      (node (ref "Q19") (pin "1") (pinfunction "1_1") (pintype "passive"))
      (node (ref "R172") (pin "2") (pinfunction "2_2") (pintype "passive"))
      (node (ref "R39") (pin "2") (pinfunction "2_2") (pintype "passive"))
      (node (ref "R40") (pin "2") (pinfunction "2_2") (pintype "passive"))
    )
    (net (code "164") (name "Net-(Q20-Pad1)") (class "Default")
      (node (ref "Q20") (pin "1") (pinfunction "1_1") (pintype "passive"))
      (node (ref "R174") (pin "2") (pinfunction "2_2") (pintype "passive"))
      (node (ref "R43") (pin "2") (pinfunction "2_2") (pintype "passive"))
      (node (ref "R44") (pin "2") (pinfunction "2_2") (pintype "passive"))
    )
    (net (code "165") (name "Net-(Q21-Pad1)") (class "Default")
      (node (ref "Q21") (pin "1") (pinfunction "1_1") (pintype "passive"))
      (node (ref "R175") (pin "2") (pinfunction "2_2") (pintype "passive"))
      (node (ref "R32") (pin "2") (pinfunction "2_2") (pintype "passive"))
      (node (ref "R45") (pin "2") (pinfunction "2_2") (pintype "passive"))
    )
    (net (code "166") (name "Net-(Q22-Pad1)") (class "Default")
      (node (ref "Q22") (pin "1") (pinfunction "1_1") (pintype "passive"))
      (node (ref "R177") (pin "1") (pinfunction "1_1") (pintype "passive"))
      (node (ref "R51") (pin "2") (pinfunction "2_2") (pintype "passive"))
      (node (ref "R56") (pin "2") (pinfunction "2_2") (pintype "passive"))
    )
    (net (code "167") (name "Net-(Q23-Pad1)") (class "Default")
      (node (ref "Q23") (pin "1") (pinfunction "1_1") (pintype "passive"))
      (node (ref "R178") (pin "1") (pinfunction "1_1") (pintype "passive"))
      (node (ref "R52") (pin "2") (pinfunction "2_2") (pintype "passive"))
      (node (ref "R57") (pin "2") (pinfunction "2_2") (pintype "passive"))
    )
    (net (code "168") (name "Net-(Q24-Pad1)") (class "Default")
      (node (ref "Q24") (pin "1") (pinfunction "1_1") (pintype "passive"))
      (node (ref "R179") (pin "1") (pinfunction "1_1") (pintype "passive"))
      (node (ref "R47") (pin "2") (pinfunction "2_2") (pintype "passive"))
      (node (ref "R54") (pin "2") (pinfunction "2_2") (pintype "passive"))
    )
    (net (code "169") (name "Net-(Q25-Pad1)") (class "Default")
      (node (ref "Q25") (pin "1") (pinfunction "1_1") (pintype "passive"))
      (node (ref "R180") (pin "1") (pinfunction "1_1") (pintype "passive"))
      (node (ref "R48") (pin "2") (pinfunction "2_2") (pintype "passive"))
      (node (ref "R55") (pin "2") (pinfunction "2_2") (pintype "passive"))
    )
    (net (code "170") (name "Net-(Q26-Pad1)") (class "Default")
      (node (ref "Q26") (pin "1") (pinfunction "1_1") (pintype "passive"))
      (node (ref "R182") (pin "1") (pinfunction "1_1") (pintype "passive"))
      (node (ref "R46") (pin "2") (pinfunction "2_2") (pintype "passive"))
      (node (ref "R58") (pin "2") (pinfunction "2_2") (pintype "passive"))
    )
    (net (code "171") (name "Net-(Q27-Pad1)") (class "Default")
      (node (ref "Q27") (pin "1") (pinfunction "1_1") (pintype "passive"))
      (node (ref "R181") (pin "1") (pinfunction "1_1") (pintype "passive"))
      (node (ref "R50") (pin "2") (pinfunction "2_2") (pintype "passive"))
      (node (ref "R60") (pin "2") (pinfunction "2_2") (pintype "passive"))
    )
    (net (code "172") (name "Net-(Q28-Pad1)") (class "Default")
      (node (ref "Q28") (pin "1") (pinfunction "1_1") (pintype "passive"))
      (node (ref "R176") (pin "2") (pinfunction "2_2") (pintype "passive"))
      (node (ref "R49") (pin "2") (pinfunction "2_2") (pintype "passive"))
      (node (ref "R59") (pin "2") (pinfunction "2_2") (pintype "passive"))
    )
    (net (code "173") (name "Net-(Q29-Pad1)") (class "Default")
      (node (ref "Q29") (pin "1") (pinfunction "1_1") (pintype "passive"))
      (node (ref "R184") (pin "2") (pinfunction "2_2") (pintype "passive"))
      (node (ref "R66") (pin "2") (pinfunction "2_2") (pintype "passive"))
      (node (ref "R67") (pin "2") (pinfunction "2_2") (pintype "passive"))
    )
    (net (code "174") (name "Net-(Q30-Pad1)") (class "Default")
      (node (ref "Q30") (pin "1") (pinfunction "1_1") (pintype "passive"))
      (node (ref "R186") (pin "2") (pinfunction "2_2") (pintype "passive"))
      (node (ref "R70") (pin "2") (pinfunction "2_2") (pintype "passive"))
      (node (ref "R71") (pin "2") (pinfunction "2_2") (pintype "passive"))
    )
    (net (code "175") (name "Net-(Q31-Pad1)") (class "Default")
      (node (ref "Q31") (pin "1") (pinfunction "1_1") (pintype "passive"))
      (node (ref "R188") (pin "2") (pinfunction "2_2") (pintype "passive"))
      (node (ref "R74") (pin "2") (pinfunction "2_2") (pintype "passive"))
      (node (ref "R75") (pin "2") (pinfunction "2_2") (pintype "passive"))
    )
    (net (code "176") (name "Net-(Q32-Pad1)") (class "Default")
      (node (ref "Q32") (pin "1") (pinfunction "1_1") (pintype "passive"))
      (node (ref "R183") (pin "2") (pinfunction "2_2") (pintype "passive"))
      (node (ref "R64") (pin "2") (pinfunction "2_2") (pintype "passive"))
      (node (ref "R65") (pin "2") (pinfunction "2_2") (pintype "passive"))
    )
    (net (code "177") (name "Net-(Q33-Pad1)") (class "Default")
      (node (ref "Q33") (pin "1") (pinfunction "1_1") (pintype "passive"))
      (node (ref "R185") (pin "2") (pinfunction "2_2") (pintype "passive"))
      (node (ref "R68") (pin "2") (pinfunction "2_2") (pintype "passive"))
      (node (ref "R69") (pin "2") (pinfunction "2_2") (pintype "passive"))
    )
    (net (code "178") (name "Net-(Q34-Pad1)") (class "Default")
      (node (ref "Q34") (pin "1") (pinfunction "1_1") (pintype "passive"))
      (node (ref "R187") (pin "2") (pinfunction "2_2") (pintype "passive"))
      (node (ref "R72") (pin "2") (pinfunction "2_2") (pintype "passive"))
      (node (ref "R73") (pin "2") (pinfunction "2_2") (pintype "passive"))
    )
    (net (code "179") (name "Net-(Q35-Pad1)") (class "Default")
      (node (ref "Q35") (pin "1") (pinfunction "1_1") (pintype "passive"))
      (node (ref "R189") (pin "2") (pinfunction "2_2") (pintype "passive"))
      (node (ref "R63") (pin "2") (pinfunction "2_2") (pintype "passive"))
      (node (ref "R76") (pin "2") (pinfunction "2_2") (pintype "passive"))
    )
    (net (code "180") (name "Net-(Q36-Pad1)") (class "Default")
      (node (ref "Q36") (pin "1") (pinfunction "1_1") (pintype "passive"))
      (node (ref "R192") (pin "1") (pinfunction "1_1") (pintype "passive"))
      (node (ref "R78") (pin "2") (pinfunction "2_2") (pintype "passive"))
      (node (ref "R85") (pin "2") (pinfunction "2_2") (pintype "passive"))
    )
    (net (code "181") (name "Net-(Q37-Pad1)") (class "Default")
      (node (ref "Q37") (pin "1") (pinfunction "1_1") (pintype "passive"))
      (node (ref "R193") (pin "1") (pinfunction "1_1") (pintype "passive"))
      (node (ref "R79") (pin "2") (pinfunction "2_2") (pintype "passive"))
      (node (ref "R86") (pin "2") (pinfunction "2_2") (pintype "passive"))
    )
    (net (code "182") (name "Net-(Q38-Pad1)") (class "Default")
      (node (ref "Q38") (pin "1") (pinfunction "1_1") (pintype "passive"))
      (node (ref "R194") (pin "1") (pinfunction "1_1") (pintype "passive"))
      (node (ref "R82") (pin "2") (pinfunction "2_2") (pintype "passive"))
      (node (ref "R87") (pin "2") (pinfunction "2_2") (pintype "passive"))
    )
    (net (code "183") (name "Net-(Q39-Pad1)") (class "Default")
      (node (ref "Q39") (pin "1") (pinfunction "1_1") (pintype "passive"))
      (node (ref "R190") (pin "1") (pinfunction "1_1") (pintype "passive"))
      (node (ref "R81") (pin "2") (pinfunction "2_2") (pintype "passive"))
      (node (ref "R91") (pin "2") (pinfunction "2_2") (pintype "passive"))
    )
    (net (code "184") (name "Net-(Q40-Pad1)") (class "Default")
      (node (ref "Q40") (pin "1") (pinfunction "1_1") (pintype "passive"))
      (node (ref "R195") (pin "1") (pinfunction "1_1") (pintype "passive"))
      (node (ref "R83") (pin "2") (pinfunction "2_2") (pintype "passive"))
      (node (ref "R88") (pin "2") (pinfunction "2_2") (pintype "passive"))
    )
    (net (code "185") (name "Net-(Q41-Pad1)") (class "Default")
      (node (ref "Q41") (pin "1") (pinfunction "1_1") (pintype "passive"))
      (node (ref "R191") (pin "1") (pinfunction "1_1") (pintype "passive"))
      (node (ref "R80") (pin "2") (pinfunction "2_2") (pintype "passive"))
      (node (ref "R90") (pin "2") (pinfunction "2_2") (pintype "passive"))
    )
    (net (code "186") (name "Net-(Q42-Pad1)") (class "Default")
      (node (ref "Q42") (pin "1") (pinfunction "1_1") (pintype "passive"))
      (node (ref "R196") (pin "1") (pinfunction "1_1") (pintype "passive"))
      (node (ref "R77") (pin "2") (pinfunction "2_2") (pintype "passive"))
      (node (ref "R89") (pin "2") (pinfunction "2_2") (pintype "passive"))
    )
    (net (code "187") (name "Net-(R114-Pad1)") (class "Default")
      (node (ref "R114") (pin "1") (pinfunction "1_1") (pintype "passive"))
      (node (ref "R115") (pin "2") (pinfunction "2_2") (pintype "passive"))
    )
    (net (code "188") (name "Net-(R115-Pad1)") (class "Default")
      (node (ref "R115") (pin "1") (pinfunction "1_1") (pintype "passive"))
      (node (ref "R116") (pin "2") (pinfunction "2_2") (pintype "passive"))
    )
    (net (code "189") (name "Net-(R116-Pad1)") (class "Default")
      (node (ref "R116") (pin "1") (pinfunction "1_1") (pintype "passive"))
      (node (ref "R117") (pin "2") (pinfunction "2_2") (pintype "passive"))
    )
    (net (code "190") (name "Net-(R118-Pad1)") (class "Default")
      (node (ref "R118") (pin "1") (pinfunction "1_1") (pintype "passive"))
      (node (ref "R119") (pin "2") (pinfunction "2_2") (pintype "passive"))
    )
    (net (code "191") (name "Net-(R119-Pad1)") (class "Default")
      (node (ref "R119") (pin "1") (pinfunction "1_1") (pintype "passive"))
      (node (ref "R120") (pin "2") (pinfunction "2_2") (pintype "passive"))
    )
    (net (code "192") (name "Net-(R120-Pad1)") (class "Default")
      (node (ref "R120") (pin "1") (pinfunction "1_1") (pintype "passive"))
      (node (ref "R121") (pin "2") (pinfunction "2_2") (pintype "passive"))
    )
    (net (code "193") (name "Net-(R122-Pad1)") (class "Default")
      (node (ref "R122") (pin "1") (pinfunction "1_1") (pintype "passive"))
      (node (ref "R123") (pin "2") (pinfunction "2_2") (pintype "passive"))
    )
    (net (code "194") (name "Net-(R123-Pad1)") (class "Default")
      (node (ref "R123") (pin "1") (pinfunction "1_1") (pintype "passive"))
      (node (ref "R124") (pin "2") (pinfunction "2_2") (pintype "passive"))
    )
    (net (code "195") (name "Net-(R124-Pad1)") (class "Default")
      (node (ref "R124") (pin "1") (pinfunction "1_1") (pintype "passive"))
      (node (ref "R125") (pin "2") (pinfunction "2_2") (pintype "passive"))
    )
    (net (code "196") (name "Source_3") (class "Default")
      (node (ref "C118") (pin "1") (pinfunction "1_1") (pintype "passive"))
      (node (ref "C119") (pin "1") (pinfunction "1_1") (pintype "passive"))
      (node (ref "C120") (pin "1") (pinfunction "1_1") (pintype "passive"))
      (node (ref "C121") (pin "1") (pinfunction "1_1") (pintype "passive"))
      (node (ref "C122") (pin "1") (pinfunction "1_1") (pintype "passive"))
      (node (ref "C123") (pin "1") (pinfunction "1_1") (pintype "passive"))
      (node (ref "C124") (pin "1") (pinfunction "1_1") (pintype "passive"))
      (node (ref "Q29") (pin "2") (pinfunction "2_2") (pintype "passive"))
      (node (ref "Q30") (pin "2") (pinfunction "2_2") (pintype "passive"))
      (node (ref "Q31") (pin "2") (pinfunction "2_2") (pintype "passive"))
      (node (ref "Q32") (pin "2") (pinfunction "2_2") (pintype "passive"))
      (node (ref "Q33") (pin "2") (pinfunction "2_2") (pintype "passive"))
      (node (ref "Q34") (pin "2") (pinfunction "2_2") (pintype "passive"))
      (node (ref "Q35") (pin "2") (pinfunction "2_2") (pintype "passive"))
      (node (ref "Q36") (pin "3") (pinfunction "3_3") (pintype "passive"))
      (node (ref "Q37") (pin "3") (pinfunction "3_3") (pintype "passive"))
      (node (ref "Q38") (pin "3") (pinfunction "3_3") (pintype "passive"))
      (node (ref "Q39") (pin "3") (pinfunction "3_3") (pintype "passive"))
      (node (ref "Q40") (pin "3") (pinfunction "3_3") (pintype "passive"))
      (node (ref "Q41") (pin "3") (pinfunction "3_3") (pintype "passive"))
      (node (ref "Q42") (pin "3") (pinfunction "3_3") (pintype "passive"))
      (node (ref "T7") (pin "1") (pinfunction "1_1") (pintype "passive"))
      (node (ref "T8") (pin "1") (pinfunction "1_1") (pintype "passive"))
      (node (ref "T9") (pin "1") (pinfunction "1_1") (pintype "passive"))
    )
  )
)
